# CrowPanel_ESP32_Display-7_0-inch-V3_0-20.net
KiCad netlist of a schematic drawn in EAGLE
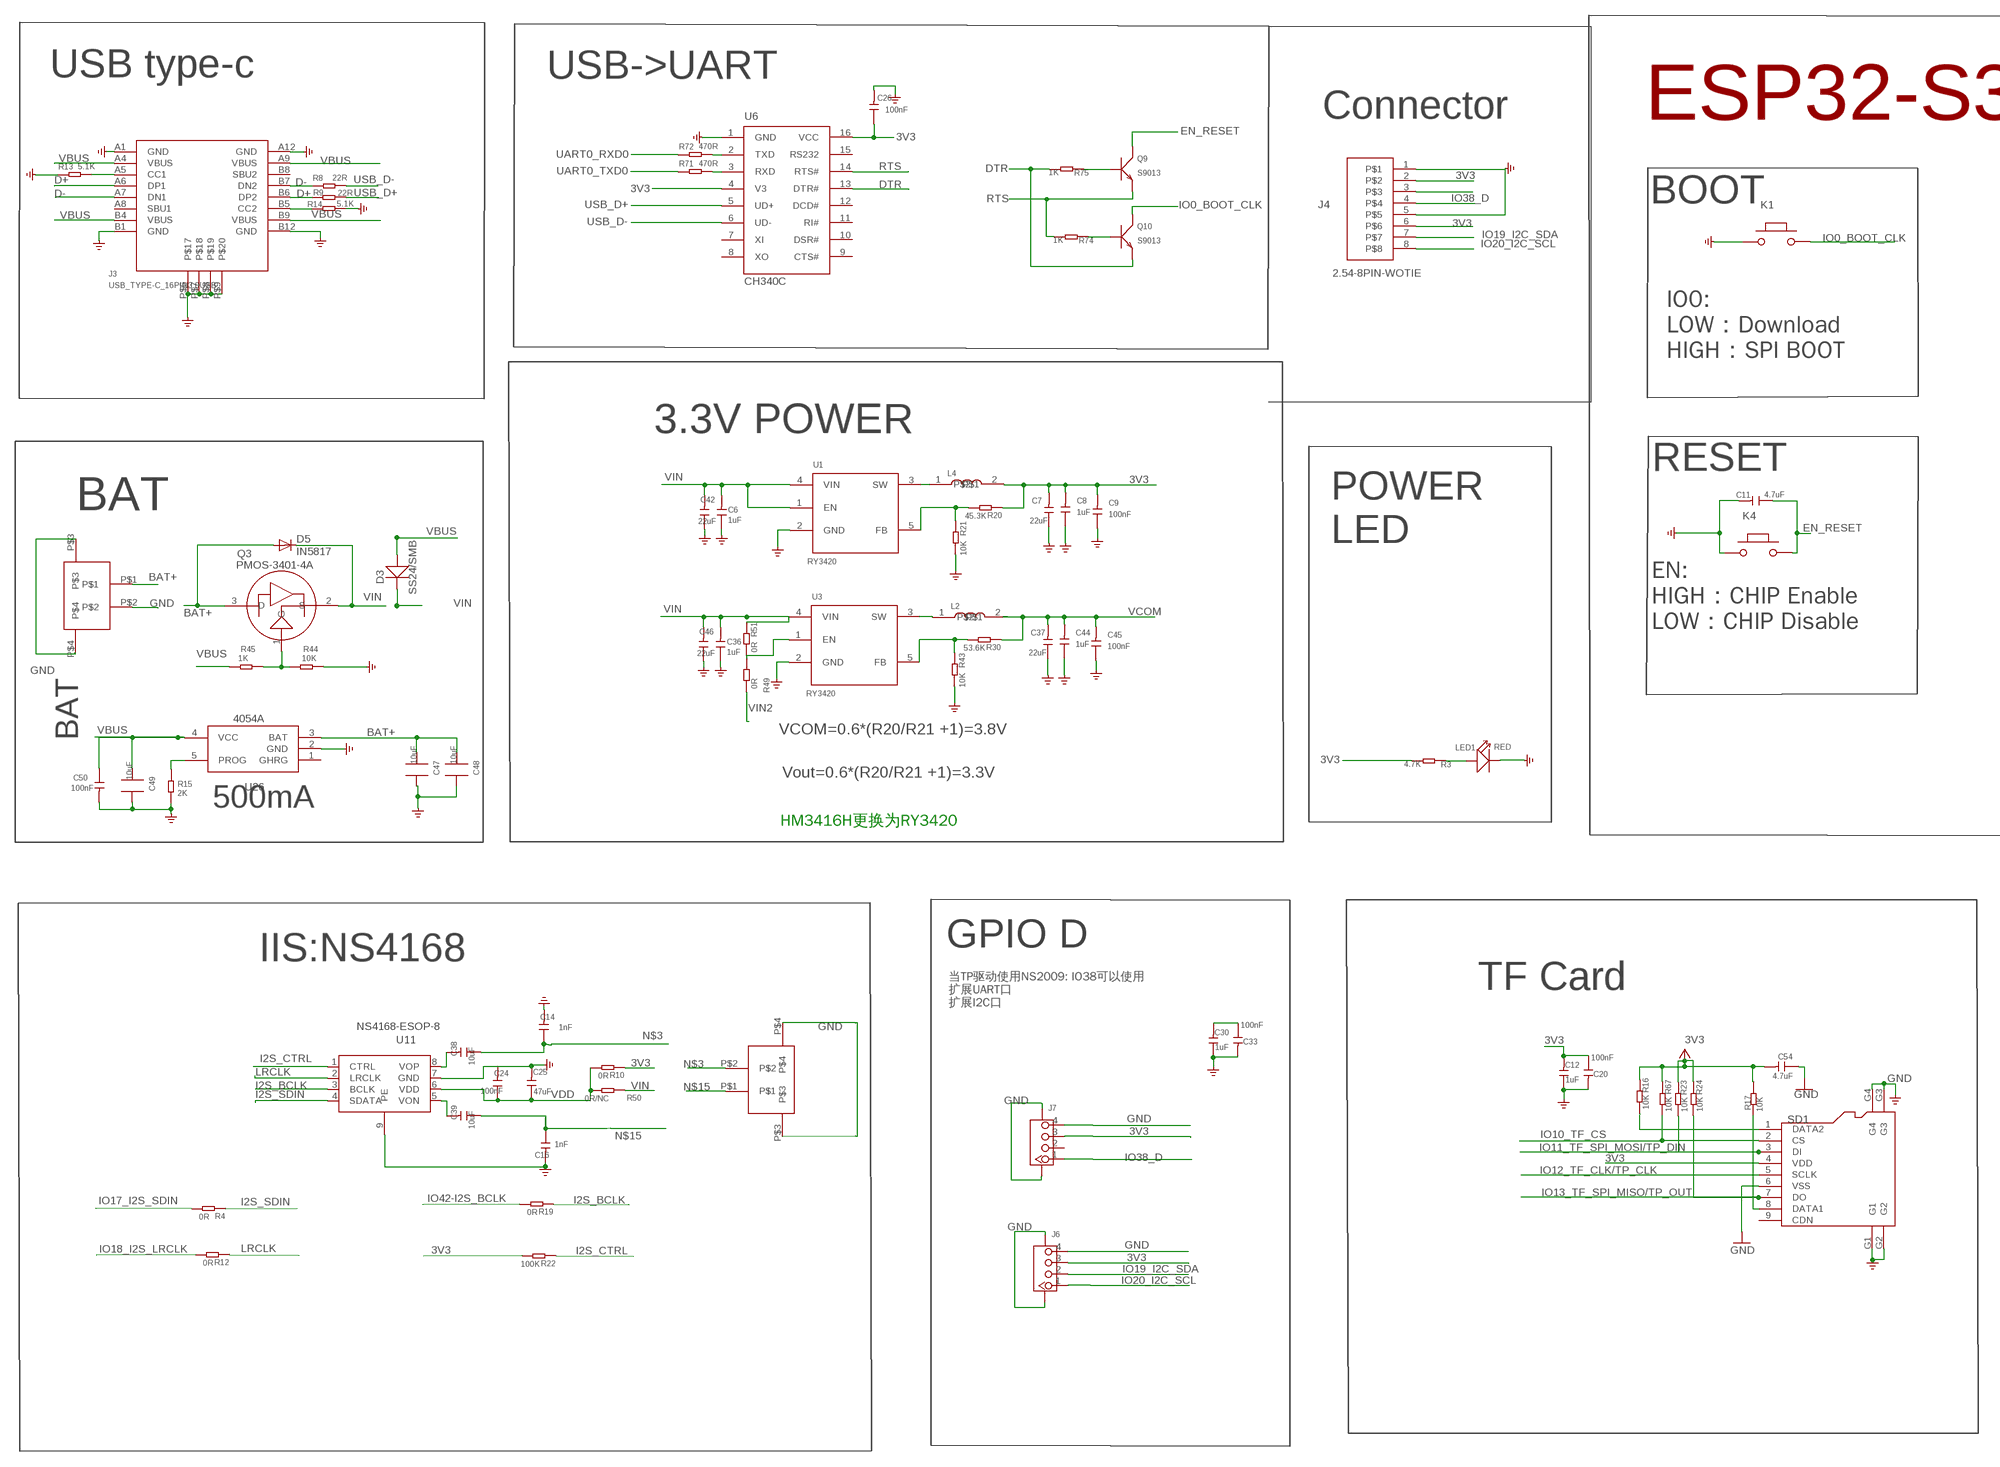
[diagram p0: schematic, sheet 1, part 1 of 2]
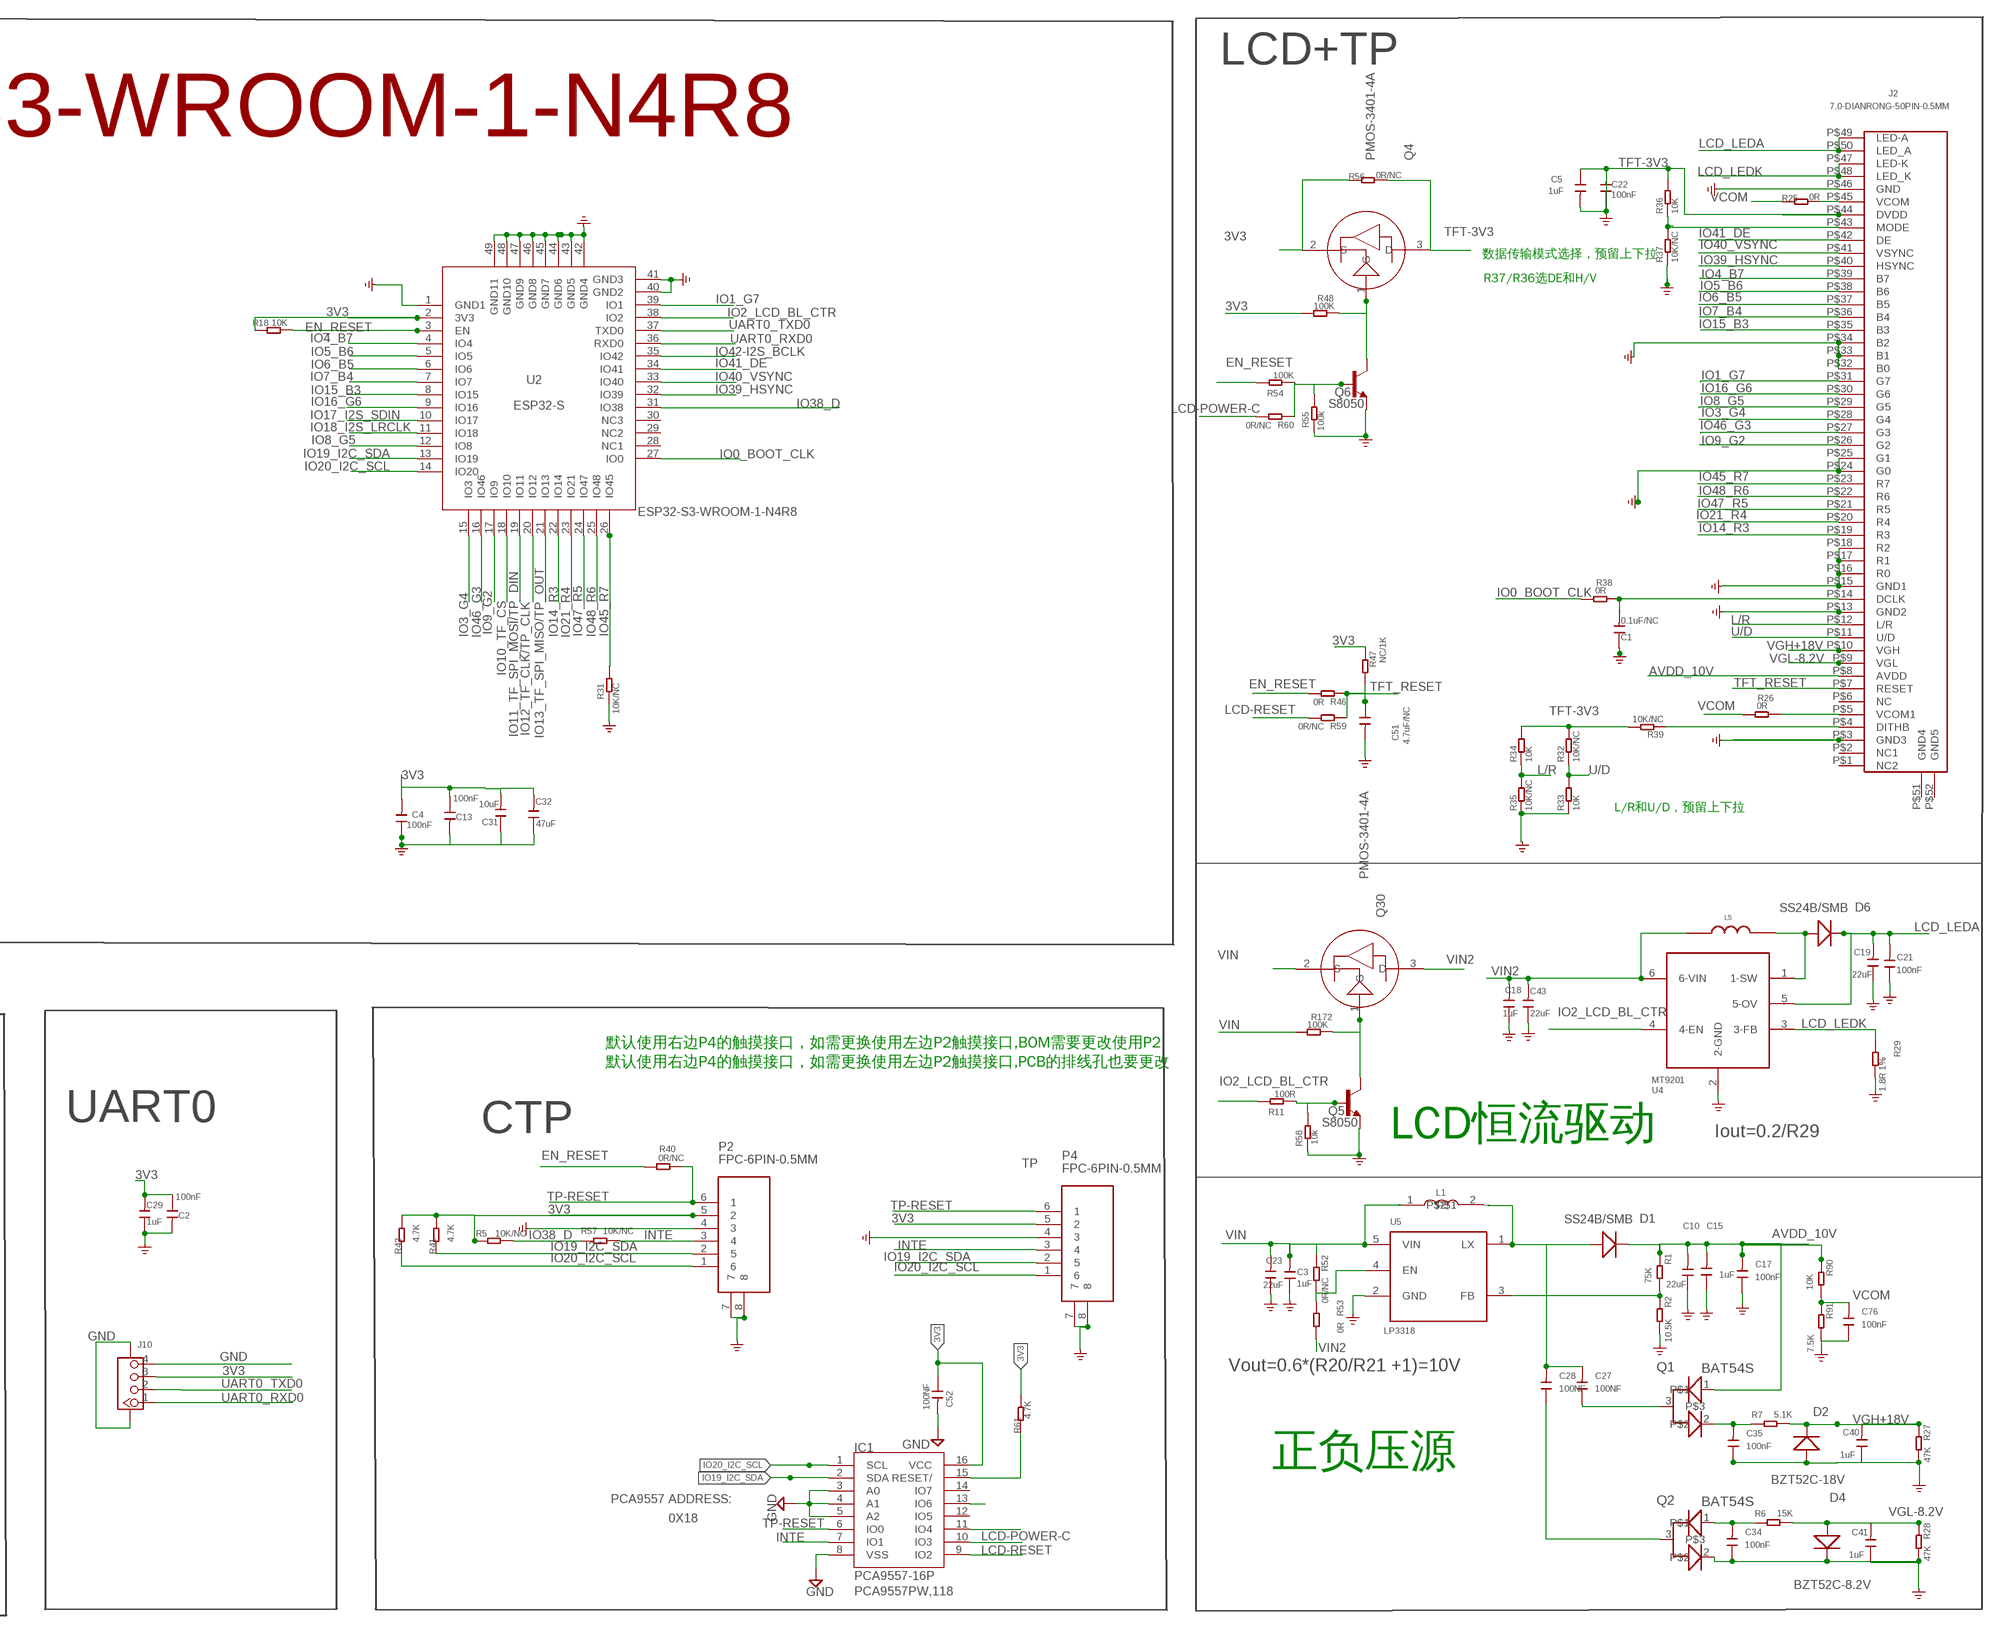
[diagram p1: schematic, sheet 1, part 2 of 2]

(export (version "E")
  (design (tool "Eeschema 10.0.6"))
  (components
    (comp (ref "C1")
      (value "0.1uF/NC")
      (footprint "eagle-import:DISCRETE_C0603")
      (libsource (lib "eagle-import") (part "DISCRETE_C-0603"))
    )
    (comp (ref "C2")
      (value "100nF")
      (footprint "eagle-import:C0603")
      (libsource (lib "eagle-import") (part "C-0603"))
    )
    (comp (ref "C3")
      (value "1uF")
      (footprint "eagle-import:0603")
      (libsource (lib "eagle-import") (part "C0603"))
    )
    (comp (ref "C4")
      (value "100nF")
      (footprint "eagle-import:C0603")
      (libsource (lib "eagle-import") (part "C-0603"))
    )
    (comp (ref "C5")
      (value "1uF")
      (footprint "eagle-import:C0603")
      (libsource (lib "eagle-import") (part "C-0603"))
    )
    (comp (ref "C6")
      (value "1uF")
      (footprint "eagle-import:0603")
      (libsource (lib "eagle-import") (part "C0603"))
    )
    (comp (ref "C7")
      (value "22uF")
      (footprint "eagle-import:0805")
      (libsource (lib "eagle-import") (part "C0805"))
    )
    (comp (ref "C8")
      (value "1uF")
      (footprint "eagle-import:0603")
      (libsource (lib "eagle-import") (part "C0603"))
    )
    (comp (ref "C9")
      (value "100nF")
      (footprint "eagle-import:0603")
      (libsource (lib "eagle-import") (part "C0603"))
    )
    (comp (ref "C10")
      (value "22uF")
      (footprint "eagle-import:0805")
      (libsource (lib "eagle-import") (part "C0805"))
    )
    (comp (ref "C11")
      (value "4.7uF")
      (footprint "eagle-import:0603")
      (libsource (lib "eagle-import") (part "C0603"))
    )
    (comp (ref "C12")
      (value "1uF")
      (footprint "eagle-import:DISCRETE_C0603")
      (libsource (lib "eagle-import") (part "A_xbj_DISCRETE_C-0603"))
    )
    (comp (ref "C13")
      (value "100nF")
      (footprint "eagle-import:C0603")
      (libsource (lib "eagle-import") (part "C-0603"))
    )
    (comp (ref "C14")
      (value "1nF")
      (footprint "eagle-import:C0603")
      (libsource (lib "eagle-import") (part "C-0603"))
    )
    (comp (ref "C15")
      (value "1uF")
      (footprint "eagle-import:0603")
      (libsource (lib "eagle-import") (part "C0603"))
    )
    (comp (ref "C16")
      (value "1nF")
      (footprint "eagle-import:C0603")
      (libsource (lib "eagle-import") (part "C-0603"))
    )
    (comp (ref "C17")
      (value "100nF")
      (footprint "eagle-import:0603")
      (libsource (lib "eagle-import") (part "C0603"))
    )
    (comp (ref "C18")
      (value "1uF")
      (footprint "eagle-import:0603")
      (libsource (lib "eagle-import") (part "C0603"))
    )
    (comp (ref "C19")
      (value "22uF")
      (footprint "eagle-import:0805")
      (libsource (lib "eagle-import") (part "C0805"))
    )
    (comp (ref "C20")
      (value "100nF")
      (footprint "eagle-import:C0603")
      (libsource (lib "eagle-import") (part "C-0603"))
    )
    (comp (ref "C21")
      (value "100nF")
      (footprint "eagle-import:0603")
      (libsource (lib "eagle-import") (part "C0603"))
    )
    (comp (ref "C22")
      (value "100nF")
      (footprint "eagle-import:C0603")
      (libsource (lib "eagle-import") (part "C-0603"))
    )
    (comp (ref "C23")
      (value "22uF")
      (footprint "eagle-import:0805")
      (libsource (lib "eagle-import") (part "C0805"))
    )
    (comp (ref "C24")
      (value "100nF")
      (footprint "eagle-import:C0603")
      (libsource (lib "eagle-import") (part "C-0603"))
    )
    (comp (ref "C25")
      (value "47uF")
      (footprint "eagle-import:0805")
      (libsource (lib "eagle-import") (part "C0805"))
    )
    (comp (ref "C26")
      (value "100nF")
      (footprint "eagle-import:0603")
      (libsource (lib "eagle-import") (part "C0603"))
    )
    (comp (ref "C27")
      (value "100NF")
      (footprint "eagle-import:0603")
      (libsource (lib "eagle-import") (part "C0603"))
    )
    (comp (ref "C28")
      (value "100NF")
      (footprint "eagle-import:0603")
      (libsource (lib "eagle-import") (part "C0603"))
    )
    (comp (ref "C29")
      (value "1uF")
      (footprint "eagle-import:DISCRETE_C0603")
      (libsource (lib "eagle-import") (part "A_xbj_DISCRETE_C-0603"))
    )
    (comp (ref "C30")
      (value "1uF")
      (footprint "eagle-import:DISCRETE_C0603")
      (libsource (lib "eagle-import") (part "A_xbj_DISCRETE_C-0603"))
    )
    (comp (ref "C31")
      (value "10uF")
      (footprint "eagle-import:DISCRETE_C0603")
      (libsource (lib "eagle-import") (part "DISCRETE_C-0603"))
    )
    (comp (ref "C32")
      (value "47uF")
      (footprint "eagle-import:0805")
      (libsource (lib "eagle-import") (part "C0805"))
    )
    (comp (ref "C33")
      (value "100nF")
      (footprint "eagle-import:C0603")
      (libsource (lib "eagle-import") (part "C-0603"))
    )
    (comp (ref "C34")
      (value "100nF")
      (footprint "eagle-import:0603")
      (libsource (lib "eagle-import") (part "C0603"))
    )
    (comp (ref "C35")
      (value "100nF")
      (footprint "eagle-import:0603")
      (libsource (lib "eagle-import") (part "C0603"))
    )
    (comp (ref "C36")
      (value "1uF")
      (footprint "eagle-import:0603")
      (libsource (lib "eagle-import") (part "C0603"))
    )
    (comp (ref "C37")
      (value "22uF")
      (footprint "eagle-import:0805")
      (libsource (lib "eagle-import") (part "C0805"))
    )
    (comp (ref "C38")
      (value "10uF")
      (footprint "eagle-import:C0603")
      (libsource (lib "eagle-import") (part "C-0603"))
    )
    (comp (ref "C39")
      (value "10uF")
      (footprint "eagle-import:C0603")
      (libsource (lib "eagle-import") (part "C-0603"))
    )
    (comp (ref "C40")
      (value "1uF")
      (footprint "eagle-import:0805")
      (libsource (lib "eagle-import") (part "C0805"))
    )
    (comp (ref "C41")
      (value "1uF")
      (footprint "eagle-import:0805")
      (libsource (lib "eagle-import") (part "C0805"))
    )
    (comp (ref "C42")
      (value "22uF")
      (footprint "eagle-import:0805")
      (libsource (lib "eagle-import") (part "C0805"))
    )
    (comp (ref "C43")
      (value "22uF")
      (footprint "eagle-import:0805")
      (libsource (lib "eagle-import") (part "C0805"))
    )
    (comp (ref "C44")
      (value "1uF")
      (footprint "eagle-import:0603")
      (libsource (lib "eagle-import") (part "C0603"))
    )
    (comp (ref "C45")
      (value "100nF")
      (footprint "eagle-import:0603")
      (libsource (lib "eagle-import") (part "C0603"))
    )
    (comp (ref "C46")
      (value "22uF")
      (footprint "eagle-import:0805")
      (libsource (lib "eagle-import") (part "C0805"))
    )
    (comp (ref "C47")
      (value "10uF")
      (footprint "eagle-import:0805_S")
      (libsource (lib "eagle-import") (part "C0805_S"))
    )
    (comp (ref "C48")
      (value "10uF")
      (footprint "eagle-import:0805_S")
      (libsource (lib "eagle-import") (part "C0805_S"))
    )
    (comp (ref "C49")
      (value "10uF")
      (footprint "eagle-import:0805_S")
      (libsource (lib "eagle-import") (part "C0805_S"))
    )
    (comp (ref "C50")
      (value "100nF")
      (footprint "eagle-import:C0603")
      (libsource (lib "eagle-import") (part "C-0603"))
    )
    (comp (ref "C51")
      (value "4.7uF/NC")
      (footprint "eagle-import:0603")
      (libsource (lib "eagle-import") (part "C0603"))
    )
    (comp (ref "C52")
      (value "100NF")
      (footprint "eagle-import:A_XBJ_0603")
      (libsource (lib "eagle-import") (part "A_XBJ_C0603"))
    )
    (comp (ref "C54")
      (value "4.7uF")
      (footprint "eagle-import:DISCRETE_C0603")
      (libsource (lib "eagle-import") (part "DISCRETE_C-0603"))
    )
    (comp (ref "C76")
      (value "100nF")
      (footprint "eagle-import:0603")
      (libsource (lib "eagle-import") (part "C0603"))
    )
    (comp (ref "D1")
      (value "SS24B/SMB")
      (footprint "eagle-import:214AB")
      (libsource (lib "eagle-import") (part "214ABDO-214AB"))
    )
    (comp (ref "D2")
      (value "BZT52C-18V")
      (footprint "eagle-import:DISCRETE_SOD123")
      (libsource (lib "eagle-import") (part "DISCRETE_D1206"))
    )
    (comp (ref "D3")
      (value "SS24/SMB")
      (footprint "eagle-import:214AB")
      (libsource (lib "eagle-import") (part "214ABDO-214AB"))
    )
    (comp (ref "D4")
      (value "BZT52C-8.2V")
      (footprint "eagle-import:DISCRETE_SOD123")
      (libsource (lib "eagle-import") (part "DISCRETE_D1206"))
    )
    (comp (ref "D5")
      (value "IN5817")
      (footprint "eagle-import:DO-214AC")
      (libsource (lib "eagle-import") (part "DIODE-DO-214AC"))
    )
    (comp (ref "D6")
      (value "SS24B/SMB")
      (footprint "eagle-import:214AB")
      (libsource (lib "eagle-import") (part "214ABDO-214AB"))
    )
    (comp (ref "IC1")
      (value "PCA9557-16P")
      (footprint "eagle-import:TSSOP16")
      (libsource (lib "eagle-import") (part "PCA9557-16P"))
    )
    (comp (ref "J1")
      (value "PH2.0WT-2PIN")
      (footprint "eagle-import:PH2.0WT-2PIN")
      (libsource (lib "eagle-import") (part "PH2.0WT-2PIN"))
    )
    (comp (ref "J2")
      (value "7.0-DIANRONG-50PIN-0.5MM")
      (footprint "eagle-import:7.0-DAINRONG-50PIN-0.5MM")
      (libsource (lib "eagle-import") (part "7.0-DIANRONG-50PIN-0.5MM"))
    )
    (comp (ref "J3")
      (value "USB_TYPE-C_16PIN3.0USB")
      (footprint "eagle-import:KEVIN_3.0TYPEC-SMD")
      (libsource (lib "eagle-import") (part "USB_TYPE-C_16PIN3.0USB"))
    )
    (comp (ref "J4")
      (value "2.54-8PIN-WOTIE")
      (footprint "eagle-import:2.54-8P-WOTIE")
      (libsource (lib "eagle-import") (part "2.54-8PIN-WOTIE"))
    )
    (comp (ref "J5")
      (value "PH2.0WT-2PIN")
      (footprint "eagle-import:PH2.0WT-2PIN")
      (libsource (lib "eagle-import") (part "PH2.0WT-2PIN"))
    )
    (comp (ref "J6")
      (value "CONNECTOR_TWIG-4P-2.0-SMD-FEMALE-REINFORCE90D")
      (footprint "eagle-import:CONNECTOR_4P-SMD-2.0-90D")
      (libsource (lib "eagle-import") (part "CONNECTOR_TWIG-4P-2.0-SMD-FEMALE-REINFORCE90D"))
    )
    (comp (ref "J7")
      (value "CONNECTOR_TWIG-4P-2.0-SMD-FEMALE-REINFORCE90D")
      (footprint "eagle-import:CONNECTOR_4P-SMD-2.0-90D")
      (libsource (lib "eagle-import") (part "CONNECTOR_TWIG-4P-2.0-SMD-FEMALE-REINFORCE90D"))
    )
    (comp (ref "J10")
      (value "CONNECTOR_TWIG-4P-2.0-SMD-FEMALE-REINFORCE90D")
      (footprint "eagle-import:CONNECTOR_4P-SMD-2.0-90D")
      (libsource (lib "eagle-import") (part "CONNECTOR_TWIG-4P-2.0-SMD-FEMALE-REINFORCE90D"))
    )
    (comp (ref "K1")
      (value "BUTTON")
      (footprint "eagle-import:157SW")
      (libsource (lib "eagle-import") (part "PB157"))
    )
    (comp (ref "K4")
      (value "BUTTON")
      (footprint "eagle-import:157SW")
      (libsource (lib "eagle-import") (part "PB157"))
    )
    (comp (ref "L1")
      (value "L-0530")
      (footprint "eagle-import:CD54_CD54")
      (libsource (lib "eagle-import") (part "L-0530"))
    )
    (comp (ref "L2")
      (value "L-0530")
      (footprint "eagle-import:CD54_CD54")
      (libsource (lib "eagle-import") (part "L-0530"))
    )
    (comp (ref "L4")
      (value "L-0530")
      (footprint "eagle-import:CD54_CD54")
      (libsource (lib "eagle-import") (part "L-0530"))
    )
    (comp (ref "L5")
      (value "CD32_6.8uH")
      (footprint "eagle-import:CD32")
      (libsource (lib "eagle-import") (part "CD32_950MA"))
    )
    (comp (ref "LED1")
      (value "RED")
      (footprint "eagle-import:DISCRETE_LED-0603")
      (libsource (lib "eagle-import") (part "DISCRETE_LED0603"))
    )
    (comp (ref "P2")
      (value "FPC-6PIN-0.5MM")
      (footprint "eagle-import:FPC-6PIN-0.5MM")
      (libsource (lib "eagle-import") (part "FPC-6PIN-0.5MM"))
    )
    (comp (ref "P4")
      (value "FPC-6PIN-0.5MM")
      (footprint "eagle-import:FPC-6PIN-0.5MM")
      (libsource (lib "eagle-import") (part "FPC-6PIN-0.5MM"))
    )
    (comp (ref "Q1")
      (value "BAT54S")
      (footprint "eagle-import:SOT23-3")
      (libsource (lib "eagle-import") (part "BAT54S"))
    )
    (comp (ref "Q2")
      (value "BAT54S")
      (footprint "eagle-import:SOT23-3")
      (libsource (lib "eagle-import") (part "BAT54S"))
    )
    (comp (ref "Q3")
      (value "PMOS-3401-4A")
      (footprint "eagle-import:SOT-23")
      (libsource (lib "eagle-import") (part "P-MOS-SOT23"))
    )
    (comp (ref "Q4")
      (value "PMOS-3401-4A")
      (footprint "eagle-import:SOT-23")
      (libsource (lib "eagle-import") (part "P-MOS-SOT23"))
    )
    (comp (ref "Q5")
      (value "S8050")
      (footprint "eagle-import:SPARKFUN_SOT23")
      (libsource (lib "eagle-import") (part "SPARKFUN_TRANSISTOR_NPNSOT23"))
    )
    (comp (ref "Q6")
      (value "S8050")
      (footprint "eagle-import:SPARKFUN_SOT23")
      (libsource (lib "eagle-import") (part "SPARKFUN_TRANSISTOR_NPNSOT23"))
    )
    (comp (ref "Q9")
      (value "S9013")
      (footprint "eagle-import:SOT23@1")
      (libsource (lib "eagle-import") (part "TRANSISTOR-NPN-SOT23"))
    )
    (comp (ref "Q10")
      (value "S9013")
      (footprint "eagle-import:SOT23@1")
      (libsource (lib "eagle-import") (part "TRANSISTOR-NPN-SOT23"))
    )
    (comp (ref "Q30")
      (value "PMOS-3401-4A")
      (footprint "eagle-import:SOT-23")
      (libsource (lib "eagle-import") (part "P-MOS-SOT23"))
    )
    (comp (ref "R1")
      (value "75K")
      (footprint "eagle-import:DISCRETE_R0603")
      (libsource (lib "eagle-import") (part "Crowtail-_LED-V2.0-20190615-01_DISCRETE_R-0603"))
    )
    (comp (ref "R2")
      (value "10.5K")
      (footprint "eagle-import:DISCRETE_R0603")
      (libsource (lib "eagle-import") (part "Crowtail-_LED-V2.0-20190615-01_DISCRETE_R-0603"))
    )
    (comp (ref "R3")
      (value "4.7K")
      (footprint "eagle-import:DISCRETE_R0603")
      (libsource (lib "eagle-import") (part "Crowtail-_LED-V2.0-20190615-01_DISCRETE_R-0603"))
    )
    (comp (ref "R4")
      (value "0R")
      (footprint "eagle-import:DISCRETE_R0603")
      (libsource (lib "eagle-import") (part "Crowtail-_LED-V2.0-20190615-01_DISCRETE_R-0603"))
    )
    (comp (ref "R5")
      (value "10K/NC")
      (footprint "eagle-import:DISCRETE_R0603")
      (libsource (lib "eagle-import") (part "Crowtail-_LED-V2.0-20190615-01_DISCRETE_R-0603"))
    )
    (comp (ref "R6")
      (value "15K")
      (footprint "eagle-import:DISCRETE_R0603")
      (libsource (lib "eagle-import") (part "Crowtail-_LED-V2.0-20190615-01_DISCRETE_R-0603"))
    )
    (comp (ref "R7")
      (value "5.1K")
      (footprint "eagle-import:DISCRETE_R0603")
      (libsource (lib "eagle-import") (part "Crowtail-_LED-V2.0-20190615-01_DISCRETE_R-0603"))
    )
    (comp (ref "R8")
      (value "22R")
      (footprint "eagle-import:DISCRETE_R0603")
      (libsource (lib "eagle-import") (part "Crowtail-_LED-V2.0-20190615-01_DISCRETE_R-0603"))
    )
    (comp (ref "R9")
      (value "22R")
      (footprint "eagle-import:DISCRETE_R0603")
      (libsource (lib "eagle-import") (part "Crowtail-_LED-V2.0-20190615-01_DISCRETE_R-0603"))
    )
    (comp (ref "R10")
      (value "0R")
      (footprint "eagle-import:DISCRETE_R0603")
      (libsource (lib "eagle-import") (part "Crowtail-_LED-V2.0-20190615-01_DISCRETE_R-0603"))
    )
    (comp (ref "R11")
      (value "100R")
      (footprint "eagle-import:R0603")
      (libsource (lib "eagle-import") (part "R0603"))
    )
    (comp (ref "R12")
      (value "0R")
      (footprint "eagle-import:DISCRETE_R0603")
      (libsource (lib "eagle-import") (part "Crowtail-_LED-V2.0-20190615-01_DISCRETE_R-0603"))
    )
    (comp (ref "R13")
      (value "5.1K")
      (footprint "eagle-import:DISCRETE_R0603")
      (libsource (lib "eagle-import") (part "Crowtail-_LED-V2.0-20190615-01_DISCRETE_R-0603"))
    )
    (comp (ref "R14")
      (value "5.1K")
      (footprint "eagle-import:DISCRETE_R0603")
      (libsource (lib "eagle-import") (part "Crowtail-_LED-V2.0-20190615-01_DISCRETE_R-0603"))
    )
    (comp (ref "R15")
      (value "2K")
      (footprint "eagle-import:DISCRETE_R0603")
      (libsource (lib "eagle-import") (part "DISCRETE_R-0603"))
    )
    (comp (ref "R16")
      (value "10K")
      (footprint "eagle-import:DISCRETE_R0603")
      (libsource (lib "eagle-import") (part "Crowtail-_LED-V2.0-20190615-01_DISCRETE_R-0603"))
    )
    (comp (ref "R17")
      (value "10K")
      (footprint "eagle-import:DISCRETE_R0603")
      (libsource (lib "eagle-import") (part "Crowtail-_LED-V2.0-20190615-01_DISCRETE_R-0603"))
    )
    (comp (ref "R18")
      (value "10K")
      (footprint "eagle-import:DISCRETE_R0603")
      (libsource (lib "eagle-import") (part "Crowtail-_LED-V2.0-20190615-01_DISCRETE_R-0603"))
    )
    (comp (ref "R19")
      (value "0R")
      (footprint "eagle-import:DISCRETE_R0603")
      (libsource (lib "eagle-import") (part "Crowtail-_LED-V2.0-20190615-01_DISCRETE_R-0603"))
    )
    (comp (ref "R20")
      (value "45.3K")
      (footprint "eagle-import:DISCRETE_R0603")
      (libsource (lib "eagle-import") (part "Crowtail-_LED-V2.0-20190615-01_DISCRETE_R-0603"))
    )
    (comp (ref "R21")
      (value "10K")
      (footprint "eagle-import:DISCRETE_R0603")
      (libsource (lib "eagle-import") (part "Crowtail-_LED-V2.0-20190615-01_DISCRETE_R-0603"))
    )
    (comp (ref "R22")
      (value "100K")
      (footprint "eagle-import:DISCRETE_R0603")
      (libsource (lib "eagle-import") (part "Crowtail-_LED-V2.0-20190615-01_DISCRETE_R-0603"))
    )
    (comp (ref "R23")
      (value "10K")
      (footprint "eagle-import:DISCRETE_R0603")
      (libsource (lib "eagle-import") (part "Crowtail-_LED-V2.0-20190615-01_DISCRETE_R-0603"))
    )
    (comp (ref "R24")
      (value "10K")
      (footprint "eagle-import:DISCRETE_R0603")
      (libsource (lib "eagle-import") (part "Crowtail-_LED-V2.0-20190615-01_DISCRETE_R-0603"))
    )
    (comp (ref "R25")
      (value "0R")
      (footprint "eagle-import:DISCRETE_R0603")
      (libsource (lib "eagle-import") (part "Crowtail-_LED-V2.0-20190615-01_DISCRETE_R-0603"))
    )
    (comp (ref "R26")
      (value "0R")
      (footprint "eagle-import:R0603")
      (libsource (lib "eagle-import") (part "R-0603"))
    )
    (comp (ref "R27")
      (value "47K")
      (footprint "eagle-import:DISCRETE_R0603")
      (libsource (lib "eagle-import") (part "Crowtail-_LED-V2.0-20190615-01_DISCRETE_R-0603"))
    )
    (comp (ref "R28")
      (value "47K")
      (footprint "eagle-import:DISCRETE_R0603")
      (libsource (lib "eagle-import") (part "Crowtail-_LED-V2.0-20190615-01_DISCRETE_R-0603"))
    )
    (comp (ref "R29")
      (value "1.8R 1%")
      (footprint "eagle-import:DISCRETE_R0603")
      (libsource (lib "eagle-import") (part "Crowtail-_LED-V2.0-20190615-01_DISCRETE_R-0603"))
    )
    (comp (ref "R30")
      (value "53.6K")
      (footprint "eagle-import:DISCRETE_R0603")
      (libsource (lib "eagle-import") (part "Crowtail-_LED-V2.0-20190615-01_DISCRETE_R-0603"))
    )
    (comp (ref "R31")
      (value "10K/NC")
      (footprint "eagle-import:R0603")
      (libsource (lib "eagle-import") (part "R0603"))
    )
    (comp (ref "R32")
      (value "10K/NC")
      (footprint "eagle-import:DISCRETE_R0603")
      (libsource (lib "eagle-import") (part "DISCRETE_R-0603"))
    )
    (comp (ref "R33")
      (value "10K")
      (footprint "eagle-import:DISCRETE_R0603")
      (libsource (lib "eagle-import") (part "DISCRETE_R-0603"))
    )
    (comp (ref "R34")
      (value "10K")
      (footprint "eagle-import:DISCRETE_R0603")
      (libsource (lib "eagle-import") (part "DISCRETE_R-0603"))
    )
    (comp (ref "R35")
      (value "10K/NC")
      (footprint "eagle-import:DISCRETE_R0603")
      (libsource (lib "eagle-import") (part "DISCRETE_R-0603"))
    )
    (comp (ref "R36")
      (value "10K")
      (footprint "eagle-import:DISCRETE_R0603")
      (libsource (lib "eagle-import") (part "DISCRETE_R-0603"))
    )
    (comp (ref "R37")
      (value "10K/NC")
      (footprint "eagle-import:DISCRETE_R0603")
      (libsource (lib "eagle-import") (part "DISCRETE_R-0603"))
    )
    (comp (ref "R38")
      (value "0R")
      (footprint "eagle-import:R0603")
      (libsource (lib "eagle-import") (part "R-0603"))
    )
    (comp (ref "R39")
      (value "10K/NC")
      (footprint "eagle-import:DISCRETE_R0603")
      (libsource (lib "eagle-import") (part "DISCRETE_R-0603"))
    )
    (comp (ref "R40")
      (value "0R/NC")
      (footprint "eagle-import:R0603")
      (libsource (lib "eagle-import") (part "R-0603"))
    )
    (comp (ref "R41")
      (value "4.7K")
      (footprint "eagle-import:DISCRETE_R0603")
      (libsource (lib "eagle-import") (part "Crowtail-_LED-V2.0-20190615-01_DISCRETE_R-0603"))
    )
    (comp (ref "R42")
      (value "4.7K")
      (footprint "eagle-import:DISCRETE_R0603")
      (libsource (lib "eagle-import") (part "Crowtail-_LED-V2.0-20190615-01_DISCRETE_R-0603"))
    )
    (comp (ref "R43")
      (value "10K")
      (footprint "eagle-import:DISCRETE_R0603")
      (libsource (lib "eagle-import") (part "Crowtail-_LED-V2.0-20190615-01_DISCRETE_R-0603"))
    )
    (comp (ref "R44")
      (value "10K")
      (footprint "eagle-import:DISCRETE_R0603")
      (libsource (lib "eagle-import") (part "DISCRETE_R-0603"))
    )
    (comp (ref "R45")
      (value "1K")
      (footprint "eagle-import:DISCRETE_R0603")
      (libsource (lib "eagle-import") (part "DISCRETE_R-0603"))
    )
    (comp (ref "R46")
      (value "0R")
      (footprint "eagle-import:DISCRETE_R0603")
      (libsource (lib "eagle-import") (part "Crowtail-_LED-V2.0-20190615-01_DISCRETE_R-0603"))
    )
    (comp (ref "R47")
      (value "NC/1K")
      (footprint "eagle-import:DISCRETE_R0603")
      (libsource (lib "eagle-import") (part "Crowtail-_LED-V2.0-20190615-01_DISCRETE_R-0603"))
    )
    (comp (ref "R48")
      (value "100K")
      (footprint "eagle-import:R0603")
      (libsource (lib "eagle-import") (part "R-0603"))
    )
    (comp (ref "R49")
      (value "0R")
      (footprint "eagle-import:DISCRETE_R0603")
      (libsource (lib "eagle-import") (part "Crowtail-_LED-V2.0-20190615-01_DISCRETE_R-0603"))
    )
    (comp (ref "R50")
      (value "0R/NC")
      (footprint "eagle-import:DISCRETE_R0603")
      (libsource (lib "eagle-import") (part "Crowtail-_LED-V2.0-20190615-01_DISCRETE_R-0603"))
    )
    (comp (ref "R51")
      (value "0R")
      (footprint "eagle-import:DISCRETE_R0603")
      (libsource (lib "eagle-import") (part "Crowtail-_LED-V2.0-20190615-01_DISCRETE_R-0603"))
    )
    (comp (ref "R52")
      (value "0R/NC")
      (footprint "eagle-import:DISCRETE_R0603")
      (libsource (lib "eagle-import") (part "Crowtail-_LED-V2.0-20190615-01_DISCRETE_R-0603"))
    )
    (comp (ref "R53")
      (value "0R")
      (footprint "eagle-import:DISCRETE_R0603")
      (libsource (lib "eagle-import") (part "Crowtail-_LED-V2.0-20190615-01_DISCRETE_R-0603"))
    )
    (comp (ref "R54")
      (value "100K")
      (footprint "eagle-import:R0603")
      (libsource (lib "eagle-import") (part "R0603"))
    )
    (comp (ref "R55")
      (value "100k")
      (footprint "eagle-import:R0603")
      (libsource (lib "eagle-import") (part "R0603"))
    )
    (comp (ref "R56")
      (value "0R/NC")
      (footprint "eagle-import:DISCRETE_R0603")
      (libsource (lib "eagle-import") (part "Crowtail-_LED-V2.0-20190615-01_DISCRETE_R-0603"))
    )
    (comp (ref "R57")
      (value "10K/NC")
      (footprint "eagle-import:DISCRETE_R0603")
      (libsource (lib "eagle-import") (part "Crowtail-_LED-V2.0-20190615-01_DISCRETE_R-0603"))
    )
    (comp (ref "R58")
      (value "10k")
      (footprint "eagle-import:R0603")
      (libsource (lib "eagle-import") (part "R0603"))
    )
    (comp (ref "R59")
      (value "0R/NC")
      (footprint "eagle-import:DISCRETE_R0603")
      (libsource (lib "eagle-import") (part "Crowtail-_LED-V2.0-20190615-01_DISCRETE_R-0603"))
    )
    (comp (ref "R60")
      (value "0R/NC")
      (footprint "eagle-import:DISCRETE_R0603")
      (libsource (lib "eagle-import") (part "Crowtail-_LED-V2.0-20190615-01_DISCRETE_R-0603"))
    )
    (comp (ref "R61")
      (value "4.7K")
      (footprint "eagle-import:DISCRETE_R0603")
      (libsource (lib "eagle-import") (part "Lora_RA-08H_Dev_DISCRETE_R-0603"))
    )
    (comp (ref "R67")
      (value "10K")
      (footprint "eagle-import:DISCRETE_R0603")
      (libsource (lib "eagle-import") (part "Crowtail-_LED-V2.0-20190615-01_DISCRETE_R-0603"))
    )
    (comp (ref "R71")
      (value "470R")
      (footprint "eagle-import:DISCRETE_R0603")
      (libsource (lib "eagle-import") (part "Crowtail-_LED-V2.0-20190615-01_DISCRETE_R-0603"))
    )
    (comp (ref "R72")
      (value "470R")
      (footprint "eagle-import:DISCRETE_R0603")
      (libsource (lib "eagle-import") (part "Crowtail-_LED-V2.0-20190615-01_DISCRETE_R-0603"))
    )
    (comp (ref "R74")
      (value "1K")
      (footprint "eagle-import:DISCRETE_R0603")
      (libsource (lib "eagle-import") (part "Crowtail-_LED-V2.0-20190615-01_DISCRETE_R-0603"))
    )
    (comp (ref "R75")
      (value "1K")
      (footprint "eagle-import:DISCRETE_R0603")
      (libsource (lib "eagle-import") (part "Crowtail-_LED-V2.0-20190615-01_DISCRETE_R-0603"))
    )
    (comp (ref "R90")
      (value "10K")
      (footprint "eagle-import:DISCRETE_R0603")
      (libsource (lib "eagle-import") (part "Crowtail-_LED-V2.0-20190615-01_DISCRETE_R-0603"))
    )
    (comp (ref "R91")
      (value "7.5K")
      (footprint "eagle-import:DISCRETE_R0603")
      (libsource (lib "eagle-import") (part "Crowtail-_LED-V2.0-20190615-01_DISCRETE_R-0603"))
    )
    (comp (ref "R172")
      (value "100K")
      (footprint "eagle-import:R0603")
      (libsource (lib "eagle-import") (part "R-0603"))
    )
    (comp (ref "SD1")
      (value "HOLDER-MICROSD-9P")
      (footprint "eagle-import:9P-SMD-W_-RING")
      (libsource (lib "eagle-import") (part "HOLDER-MICROSD-9P"))
    )
    (comp (ref "U1")
      (value "RY3420")
      (footprint "eagle-import:A_XBJ_SOT23-5")
      (libsource (lib "eagle-import") (part "A_XBJ_HM3420B"))
    )
    (comp (ref "U2")
      (value "ESP32-S")
      (footprint "eagle-import:ESP32-S3")
      (fields (field (name "U2") "ESP32-S3-WROOM-1-N4R8"))
      (libsource (lib "eagle-import") (part "ESP32-S"))
    )
    (comp (ref "U3")
      (value "RY3420")
      (footprint "eagle-import:A_XBJ_SOT23-5")
      (libsource (lib "eagle-import") (part "A_XBJ_HM3420B"))
    )
    (comp (ref "U4")
      (value "MT9201")
      (footprint "eagle-import:SOT23-6")
      (libsource (lib "eagle-import") (part "MT9201"))
    )
    (comp (ref "U5")
      (value "LP3318")
      (footprint "eagle-import:LP3318_SOT23-5")
      (libsource (lib "eagle-import") (part "LP3318"))
    )
    (comp (ref "U6")
      (value "CH340C")
      (footprint "eagle-import:SOP-16")
      (libsource (lib "eagle-import") (part "CH340G"))
    )
    (comp (ref "U11")
      (value "NS4168-ESOP-8")
      (footprint "eagle-import:NS4168-ESOP-8")
      (libsource (lib "eagle-import") (part "NS4168-ESOP-8"))
    )
    (comp (ref "U26")
      (value "4054A")
      (footprint "eagle-import:SOP23-5")
      (libsource (lib "eagle-import") (part "4054A"))
    )
  )
  (nets
    (net (code "1") (name "/AVDD_10V") (class "Default")
      (node (ref "C10") (pin "2") (pinfunction "2_2") (pintype "passive"))
      (node (ref "C15") (pin "2") (pinfunction "2_2") (pintype "passive"))
      (node (ref "C17") (pin "2") (pinfunction "2_2") (pintype "passive"))
      (node (ref "D1") (pin "2") (pinfunction "-_2") (pintype "passive"))
      (node (ref "J2") (pin "P$8") (pinfunction "AVDD_P$8") (pintype "bidirectional"))
      (node (ref "Q1") (pin "1") (pinfunction "P$1_1") (pintype "bidirectional"))
      (node (ref "R1") (pin "1") (pinfunction "1_1") (pintype "passive"))
      (node (ref "R90") (pin "1") (pinfunction "1_1") (pintype "passive"))
    )
    (net (code "2") (name "/BAT+") (class "Default")
      (node (ref "C47") (pin "2") (pinfunction "2_2") (pintype "bidirectional"))
      (node (ref "C48") (pin "2") (pinfunction "2_2") (pintype "bidirectional"))
      (node (ref "D5") (pin "A") (pinfunction "A_A") (pintype "passive"))
      (node (ref "J1") (pin "P$1") (pinfunction "P$1_P$1") (pintype "bidirectional"))
      (node (ref "Q3") (pin "3") (pinfunction "D_3") (pintype "bidirectional"))
      (node (ref "U26") (pin "3") (pinfunction "BAT_3") (pintype "bidirectional"))
    )
    (net (code "3") (name "/D+") (class "Default")
      (node (ref "J3") (pin "A6") (pinfunction "DP1_A6") (pintype "bidirectional"))
      (node (ref "J3") (pin "B6") (pinfunction "DP2_B6") (pintype "bidirectional"))
      (node (ref "R9") (pin "1") (pinfunction "1_1") (pintype "passive"))
    )
    (net (code "4") (name "/D-") (class "Default")
      (node (ref "J3") (pin "A7") (pinfunction "DN1_A7") (pintype "bidirectional"))
      (node (ref "J3") (pin "B7") (pinfunction "DN2_B7") (pintype "bidirectional"))
      (node (ref "R8") (pin "1") (pinfunction "1_1") (pintype "passive"))
    )
    (net (code "5") (name "/DTR") (class "Default")
      (node (ref "Q10") (pin "2") (pinfunction "E_2") (pintype "passive"))
      (node (ref "R75") (pin "2") (pinfunction "2_2") (pintype "passive"))
      (node (ref "U6") (pin "13") (pinfunction "DTR#_13") (pintype "bidirectional"))
    )
    (net (code "6") (name "/EN_RESET") (class "Default")
      (node (ref "C11") (pin "1") (pinfunction "1_1") (pintype "passive"))
      (node (ref "K4") (pin "2") (pinfunction "2_2") (pintype "passive"))
      (node (ref "Q9") (pin "3") (pinfunction "C_3") (pintype "passive"))
      (node (ref "R18") (pin "2") (pinfunction "2_2") (pintype "passive"))
      (node (ref "R40") (pin "1") (pinfunction "1_1") (pintype "passive"))
      (node (ref "R46") (pin "2") (pinfunction "2_2") (pintype "passive"))
      (node (ref "R54") (pin "2") (pinfunction "2_2") (pintype "passive"))
      (node (ref "U2") (pin "3") (pinfunction "EN_3") (pintype "bidirectional"))
    )
    (net (code "7") (name "/I2S_BCLK") (class "Default")
      (node (ref "R19") (pin "1") (pinfunction "1_1") (pintype "passive"))
      (node (ref "U11") (pin "3") (pinfunction "BCLK_3") (pintype "bidirectional"))
    )
    (net (code "8") (name "/I2S_CTRL") (class "Default")
      (node (ref "R22") (pin "1") (pinfunction "1_1") (pintype "passive"))
      (node (ref "U11") (pin "1") (pinfunction "CTRL_1") (pintype "bidirectional"))
    )
    (net (code "9") (name "/I2S_SDIN") (class "Default")
      (node (ref "R4") (pin "1") (pinfunction "1_1") (pintype "passive"))
      (node (ref "U11") (pin "4") (pinfunction "SDATA_4") (pintype "bidirectional"))
    )
    (net (code "10") (name "/INTE") (class "Default")
      (node (ref "IC1") (pin "7") (pinfunction "IO1_7") (pintype "bidirectional"))
      (node (ref "P2") (pin "3") (pinfunction "4_3") (pintype "bidirectional"))
      (node (ref "P4") (pin "3") (pinfunction "4_3") (pintype "bidirectional"))
      (node (ref "R57") (pin "2") (pinfunction "2_2") (pintype "passive"))
    )
    (net (code "11") (name "/IO0_BOOT_CLK") (class "Default")
      (node (ref "K1") (pin "2") (pinfunction "2_2") (pintype "passive"))
      (node (ref "Q10") (pin "3") (pinfunction "C_3") (pintype "passive"))
      (node (ref "R38") (pin "1") (pinfunction "1_1") (pintype "passive"))
      (node (ref "U2") (pin "27") (pinfunction "IO0_27") (pintype "bidirectional"))
    )
    (net (code "12") (name "/IO1_G7") (class "Default")
      (node (ref "J2") (pin "P$31") (pinfunction "G7_P$31") (pintype "bidirectional"))
      (node (ref "U2") (pin "39") (pinfunction "IO1_39") (pintype "bidirectional"))
    )
    (net (code "13") (name "/IO2_LCD_BL_CTR") (class "Default")
      (node (ref "R11") (pin "2") (pinfunction "2_2") (pintype "passive"))
      (node (ref "U2") (pin "38") (pinfunction "IO2_38") (pintype "bidirectional"))
      (node (ref "U4") (pin "4") (pinfunction "4-EN_4") (pintype "bidirectional"))
    )
    (net (code "14") (name "/IO3_G4") (class "Default")
      (node (ref "J2") (pin "P$28") (pinfunction "G4_P$28") (pintype "bidirectional"))
      (node (ref "U2") (pin "15") (pinfunction "IO3_15") (pintype "bidirectional"))
    )
    (net (code "15") (name "/IO4_B7") (class "Default")
      (node (ref "J2") (pin "P$39") (pinfunction "B7_P$39") (pintype "bidirectional"))
      (node (ref "U2") (pin "4") (pinfunction "IO4_4") (pintype "bidirectional"))
    )
    (net (code "16") (name "/IO5_B6") (class "Default")
      (node (ref "J2") (pin "P$38") (pinfunction "B6_P$38") (pintype "bidirectional"))
      (node (ref "U2") (pin "5") (pinfunction "IO5_5") (pintype "bidirectional"))
    )
    (net (code "17") (name "/IO6_B5") (class "Default")
      (node (ref "J2") (pin "P$37") (pinfunction "B5_P$37") (pintype "bidirectional"))
      (node (ref "U2") (pin "6") (pinfunction "IO6_6") (pintype "bidirectional"))
    )
    (net (code "18") (name "/IO7_B4") (class "Default")
      (node (ref "J2") (pin "P$36") (pinfunction "B4_P$36") (pintype "bidirectional"))
      (node (ref "U2") (pin "7") (pinfunction "IO7_7") (pintype "bidirectional"))
    )
    (net (code "19") (name "/IO8_G5") (class "Default")
      (node (ref "J2") (pin "P$29") (pinfunction "G5_P$29") (pintype "bidirectional"))
      (node (ref "U2") (pin "12") (pinfunction "IO8_12") (pintype "bidirectional"))
    )
    (net (code "20") (name "/IO9_G2") (class "Default")
      (node (ref "J2") (pin "P$26") (pinfunction "G2_P$26") (pintype "bidirectional"))
      (node (ref "U2") (pin "17") (pinfunction "IO9_17") (pintype "bidirectional"))
    )
    (net (code "21") (name "/IO10_TF_CS") (class "Default")
      (node (ref "R67") (pin "2") (pinfunction "2_2") (pintype "passive"))
      (node (ref "SD1") (pin "2") (pinfunction "CS_2") (pintype "bidirectional"))
      (node (ref "U2") (pin "18") (pinfunction "IO10_18") (pintype "bidirectional"))
    )
    (net (code "22") (name "/IO11_TF_SPI_MOSI{slash}TP_DIN") (class "Default")
      (node (ref "R23") (pin "2") (pinfunction "2_2") (pintype "passive"))
      (node (ref "SD1") (pin "3") (pinfunction "DI_3") (pintype "bidirectional"))
      (node (ref "U2") (pin "19") (pinfunction "IO11_19") (pintype "bidirectional"))
    )
    (net (code "23") (name "/IO12_TF_CLK{slash}TP_CLK") (class "Default")
      (node (ref "SD1") (pin "5") (pinfunction "SCLK_5") (pintype "bidirectional"))
      (node (ref "U2") (pin "20") (pinfunction "IO12_20") (pintype "bidirectional"))
    )
    (net (code "24") (name "/IO13_TF_SPI_MISO{slash}TP_OUT") (class "Default")
      (node (ref "R24") (pin "2") (pinfunction "2_2") (pintype "passive"))
      (node (ref "SD1") (pin "7") (pinfunction "DO_7") (pintype "bidirectional"))
      (node (ref "U2") (pin "21") (pinfunction "IO13_21") (pintype "bidirectional"))
    )
    (net (code "25") (name "/IO14_R3") (class "Default")
      (node (ref "J2") (pin "P$19") (pinfunction "R3_P$19") (pintype "bidirectional"))
      (node (ref "U2") (pin "22") (pinfunction "IO14_22") (pintype "bidirectional"))
    )
    (net (code "26") (name "/IO15_B3") (class "Default")
      (node (ref "J2") (pin "P$35") (pinfunction "B3_P$35") (pintype "bidirectional"))
      (node (ref "U2") (pin "8") (pinfunction "IO15_8") (pintype "bidirectional"))
    )
    (net (code "27") (name "/IO16_G6") (class "Default")
      (node (ref "J2") (pin "P$30") (pinfunction "G6_P$30") (pintype "bidirectional"))
      (node (ref "U2") (pin "9") (pinfunction "IO16_9") (pintype "bidirectional"))
    )
    (net (code "28") (name "/IO17_I2S_SDIN") (class "Default")
      (node (ref "R4") (pin "2") (pinfunction "2_2") (pintype "passive"))
      (node (ref "U2") (pin "10") (pinfunction "IO17_10") (pintype "bidirectional"))
    )
    (net (code "29") (name "/IO18_I2S_LRCLK") (class "Default")
      (node (ref "R12") (pin "2") (pinfunction "2_2") (pintype "passive"))
      (node (ref "U2") (pin "11") (pinfunction "IO18_11") (pintype "bidirectional"))
    )
    (net (code "30") (name "/IO21_R4") (class "Default")
      (node (ref "J2") (pin "P$20") (pinfunction "R4_P$20") (pintype "bidirectional"))
      (node (ref "U2") (pin "23") (pinfunction "IO21_23") (pintype "bidirectional"))
    )
    (net (code "31") (name "/IO38_D") (class "Default")
      (node (ref "J4") (pin "4") (pinfunction "P$4_4") (pintype "bidirectional"))
      (node (ref "J7") (pin "1") (pinfunction "1_1") (pintype "bidirectional"))
      (node (ref "R5") (pin "2") (pinfunction "2_2") (pintype "passive"))
      (node (ref "R57") (pin "1") (pinfunction "1_1") (pintype "passive"))
      (node (ref "U2") (pin "31") (pinfunction "IO38_31") (pintype "bidirectional"))
    )
    (net (code "32") (name "/IO39_HSYNC") (class "Default")
      (node (ref "J2") (pin "P$40") (pinfunction "HSYNC_P$40") (pintype "bidirectional"))
      (node (ref "U2") (pin "32") (pinfunction "IO39_32") (pintype "bidirectional"))
    )
    (net (code "33") (name "/IO40_VSYNC") (class "Default")
      (node (ref "J2") (pin "P$41") (pinfunction "VSYNC_P$41") (pintype "bidirectional"))
      (node (ref "U2") (pin "33") (pinfunction "IO40_33") (pintype "bidirectional"))
    )
    (net (code "34") (name "/IO41_DE") (class "Default")
      (node (ref "J2") (pin "P$42") (pinfunction "DE_P$42") (pintype "bidirectional"))
      (node (ref "U2") (pin "34") (pinfunction "IO41_34") (pintype "bidirectional"))
    )
    (net (code "35") (name "/IO42-I2S_BCLK") (class "Default")
      (node (ref "R19") (pin "2") (pinfunction "2_2") (pintype "passive"))
      (node (ref "U2") (pin "35") (pinfunction "IO42_35") (pintype "bidirectional"))
    )
    (net (code "36") (name "/IO45_R7") (class "Default")
      (node (ref "J2") (pin "P$23") (pinfunction "R7_P$23") (pintype "bidirectional"))
      (node (ref "R31") (pin "2") (pinfunction "2_2") (pintype "passive"))
      (node (ref "U2") (pin "26") (pinfunction "IO45_26") (pintype "bidirectional"))
    )
    (net (code "37") (name "/IO46_G3") (class "Default")
      (node (ref "J2") (pin "P$27") (pinfunction "G3_P$27") (pintype "bidirectional"))
      (node (ref "U2") (pin "16") (pinfunction "IO46_16") (pintype "bidirectional"))
    )
    (net (code "38") (name "/IO47_R5") (class "Default")
      (node (ref "J2") (pin "P$21") (pinfunction "R5_P$21") (pintype "bidirectional"))
      (node (ref "U2") (pin "24") (pinfunction "IO47_24") (pintype "bidirectional"))
    )
    (net (code "39") (name "/IO48_R6") (class "Default")
      (node (ref "J2") (pin "P$22") (pinfunction "R6_P$22") (pintype "bidirectional"))
      (node (ref "U2") (pin "25") (pinfunction "IO48_25") (pintype "bidirectional"))
    )
    (net (code "40") (name "/LCD-POWER-C") (class "Default")
      (node (ref "IC1") (pin "10") (pinfunction "IO3_10") (pintype "bidirectional"))
      (node (ref "R60") (pin "2") (pinfunction "2_2") (pintype "passive"))
    )
    (net (code "41") (name "/LCD-RESET") (class "Default")
      (node (ref "IC1") (pin "9") (pinfunction "IO2_9") (pintype "bidirectional"))
      (node (ref "R59") (pin "2") (pinfunction "2_2") (pintype "passive"))
    )
    (net (code "42") (name "/LCD_LEDA") (class "Default")
      (node (ref "C19") (pin "2") (pinfunction "2_2") (pintype "passive"))
      (node (ref "C21") (pin "2") (pinfunction "2_2") (pintype "passive"))
      (node (ref "D6") (pin "2") (pinfunction "-_2") (pintype "passive"))
      (node (ref "J2") (pin "P$49") (pinfunction "LED-A_P$49") (pintype "bidirectional"))
      (node (ref "J2") (pin "P$50") (pinfunction "LED_A_P$50") (pintype "bidirectional"))
      (node (ref "U4") (pin "5") (pinfunction "5-OV_5") (pintype "bidirectional"))
    )
    (net (code "43") (name "/LCD_LEDK") (class "Default")
      (node (ref "J2") (pin "P$47") (pinfunction "LED-K_P$47") (pintype "bidirectional"))
      (node (ref "J2") (pin "P$48") (pinfunction "LED_K_P$48") (pintype "bidirectional"))
      (node (ref "R29") (pin "1") (pinfunction "1_1") (pintype "passive"))
      (node (ref "U4") (pin "3") (pinfunction "3-FB_3") (pintype "bidirectional"))
    )
    (net (code "44") (name "/LRCLK") (class "Default")
      (node (ref "R12") (pin "1") (pinfunction "1_1") (pintype "passive"))
      (node (ref "U11") (pin "2") (pinfunction "LRCLK_2") (pintype "bidirectional"))
    )
    (net (code "45") (name "/L{slash}R") (class "Default")
      (node (ref "J2") (pin "P$12") (pinfunction "L/R_P$12") (pintype "bidirectional"))
      (node (ref "R34") (pin "1") (pinfunction "1_1") (pintype "passive"))
      (node (ref "R35") (pin "2") (pinfunction "2_2") (pintype "passive"))
    )
    (net (code "46") (name "/N$3") (class "Default")
      (node (ref "C14") (pin "1") (pinfunction "1_1") (pintype "passive"))
      (node (ref "C38") (pin "1") (pinfunction "1_1") (pintype "passive"))
      (node (ref "J5") (pin "P$2") (pinfunction "P$2_P$2") (pintype "bidirectional"))
    )
    (net (code "47") (name "/N$15") (class "Default")
      (node (ref "C16") (pin "1") (pinfunction "1_1") (pintype "passive"))
      (node (ref "C39") (pin "1") (pinfunction "1_1") (pintype "passive"))
      (node (ref "J5") (pin "P$1") (pinfunction "P$1_P$1") (pintype "bidirectional"))
    )
    (net (code "48") (name "/RTS") (class "Default")
      (node (ref "Q9") (pin "2") (pinfunction "E_2") (pintype "passive"))
      (node (ref "R74") (pin "2") (pinfunction "2_2") (pintype "passive"))
      (node (ref "U6") (pin "14") (pinfunction "RTS#_14") (pintype "bidirectional"))
    )
    (net (code "49") (name "/TFT-3V3") (class "Default")
      (node (ref "C22") (pin "2") (pinfunction "2_2") (pintype "passive"))
      (node (ref "C5") (pin "1") (pinfunction "1_1") (pintype "passive"))
      (node (ref "J2") (pin "P$44") (pinfunction "DVDD_P$44") (pintype "bidirectional"))
      (node (ref "Q4") (pin "3") (pinfunction "D_3") (pintype "bidirectional"))
      (node (ref "R32") (pin "2") (pinfunction "2_2") (pintype "passive"))
      (node (ref "R34") (pin "2") (pinfunction "2_2") (pintype "passive"))
      (node (ref "R36") (pin "2") (pinfunction "2_2") (pintype "passive"))
      (node (ref "R39") (pin "2") (pinfunction "2_2") (pintype "passive"))
      (node (ref "R56") (pin "2") (pinfunction "2_2") (pintype "passive"))
    )
    (net (code "50") (name "/TFT_RESET") (class "Default")
      (node (ref "C51") (pin "1") (pinfunction "1_1") (pintype "passive"))
      (node (ref "J2") (pin "P$7") (pinfunction "RESET_P$7") (pintype "bidirectional"))
      (node (ref "R46") (pin "1") (pinfunction "1_1") (pintype "passive"))
      (node (ref "R47") (pin "1") (pinfunction "1_1") (pintype "passive"))
      (node (ref "R59") (pin "1") (pinfunction "1_1") (pintype "passive"))
    )
    (net (code "51") (name "/TP-RESET") (class "Default")
      (node (ref "IC1") (pin "6") (pinfunction "IO0_6") (pintype "bidirectional"))
      (node (ref "P2") (pin "6") (pinfunction "1_6") (pintype "bidirectional"))
      (node (ref "P4") (pin "6") (pinfunction "1_6") (pintype "bidirectional"))
      (node (ref "R40") (pin "2") (pinfunction "2_2") (pintype "passive"))
    )
    (net (code "52") (name "/UART0_RXD0") (class "Default")
      (node (ref "J10") (pin "1") (pinfunction "1_1") (pintype "bidirectional"))
      (node (ref "R72") (pin "1") (pinfunction "1_1") (pintype "passive"))
      (node (ref "U2") (pin "36") (pinfunction "RXD0_36") (pintype "bidirectional"))
    )
    (net (code "53") (name "/UART0_TXD0") (class "Default")
      (node (ref "J10") (pin "2") (pinfunction "2_2") (pintype "bidirectional"))
      (node (ref "R71") (pin "1") (pinfunction "1_1") (pintype "passive"))
      (node (ref "U2") (pin "37") (pinfunction "TXD0_37") (pintype "bidirectional"))
    )
    (net (code "54") (name "/USB_D+") (class "Default")
      (node (ref "R9") (pin "2") (pinfunction "2_2") (pintype "passive"))
      (node (ref "U6") (pin "5") (pinfunction "UD+_5") (pintype "bidirectional"))
    )
    (net (code "55") (name "/USB_D-") (class "Default")
      (node (ref "R8") (pin "2") (pinfunction "2_2") (pintype "passive"))
      (node (ref "U6") (pin "6") (pinfunction "UD-_6") (pintype "bidirectional"))
    )
    (net (code "56") (name "/U{slash}D") (class "Default")
      (node (ref "J2") (pin "P$11") (pinfunction "U/D_P$11") (pintype "bidirectional"))
      (node (ref "R32") (pin "1") (pinfunction "1_1") (pintype "passive"))
      (node (ref "R33") (pin "2") (pinfunction "2_2") (pintype "passive"))
    )
    (net (code "57") (name "/VBUS") (class "Default")
      (node (ref "C49") (pin "2") (pinfunction "2_2") (pintype "bidirectional"))
      (node (ref "C50") (pin "1") (pinfunction "1_1") (pintype "passive"))
      (node (ref "D3") (pin "1") (pinfunction "+_1") (pintype "passive"))
      (node (ref "J3") (pin "A4") (pinfunction "VBUS_A4") (pintype "bidirectional"))
      (node (ref "J3") (pin "A9") (pinfunction "VBUS_A9") (pintype "bidirectional"))
      (node (ref "J3") (pin "B4") (pinfunction "VBUS_B4") (pintype "bidirectional"))
      (node (ref "J3") (pin "B9") (pinfunction "VBUS_B9") (pintype "bidirectional"))
      (node (ref "R45") (pin "2") (pinfunction "2_2") (pintype "passive"))
      (node (ref "U26") (pin "4") (pinfunction "VCC_4") (pintype "bidirectional"))
    )
    (net (code "58") (name "/VCOM") (class "Default")
      (node (ref "C37") (pin "2") (pinfunction "2_2") (pintype "passive"))
      (node (ref "C44") (pin "2") (pinfunction "2_2") (pintype "passive"))
      (node (ref "C45") (pin "2") (pinfunction "2_2") (pintype "passive"))
      (node (ref "C76") (pin "2") (pinfunction "2_2") (pintype "passive"))
      (node (ref "L2") (pin "2") (pinfunction "P$2_2") (pintype "bidirectional"))
      (node (ref "R25") (pin "1") (pinfunction "1_1") (pintype "passive"))
      (node (ref "R26") (pin "1") (pinfunction "1_1") (pintype "passive"))
      (node (ref "R30") (pin "1") (pinfunction "1_1") (pintype "passive"))
      (node (ref "R90") (pin "2") (pinfunction "2_2") (pintype "passive"))
      (node (ref "R91") (pin "1") (pinfunction "1_1") (pintype "passive"))
    )
    (net (code "59") (name "/VDD") (class "Default")
      (node (ref "C24") (pin "1") (pinfunction "1_1") (pintype "passive"))
      (node (ref "C25") (pin "1") (pinfunction "1_1") (pintype "passive"))
      (node (ref "R10") (pin "2") (pinfunction "2_2") (pintype "passive"))
      (node (ref "R50") (pin "2") (pinfunction "2_2") (pintype "passive"))
      (node (ref "U11") (pin "6") (pinfunction "VDD_6") (pintype "bidirectional"))
    )
    (net (code "60") (name "/VGH+18V") (class "Default")
      (node (ref "C40") (pin "2") (pinfunction "2_2") (pintype "passive"))
      (node (ref "D2") (pin "-") (pinfunction "-_-") (pintype "passive"))
      (node (ref "J2") (pin "P$10") (pinfunction "VGH_P$10") (pintype "bidirectional"))
      (node (ref "R27") (pin "1") (pinfunction "1_1") (pintype "passive"))
      (node (ref "R7") (pin "2") (pinfunction "2_2") (pintype "passive"))
    )
    (net (code "61") (name "/VGL-8.2V") (class "Default")
      (node (ref "C41") (pin "2") (pinfunction "2_2") (pintype "passive"))
      (node (ref "D4") (pin "+") (pinfunction "+_+") (pintype "passive"))
      (node (ref "J2") (pin "P$9") (pinfunction "VGL_P$9") (pintype "bidirectional"))
      (node (ref "R28") (pin "1") (pinfunction "1_1") (pintype "passive"))
      (node (ref "R6") (pin "2") (pinfunction "2_2") (pintype "passive"))
    )
    (net (code "62") (name "/VIN") (class "Default")
      (node (ref "C23") (pin "2") (pinfunction "2_2") (pintype "passive"))
      (node (ref "C3") (pin "2") (pinfunction "2_2") (pintype "passive"))
      (node (ref "C36") (pin "2") (pinfunction "2_2") (pintype "passive"))
      (node (ref "C42") (pin "2") (pinfunction "2_2") (pintype "passive"))
      (node (ref "C46") (pin "2") (pinfunction "2_2") (pintype "passive"))
      (node (ref "C6") (pin "2") (pinfunction "2_2") (pintype "passive"))
      (node (ref "D3") (pin "2") (pinfunction "-_2") (pintype "passive"))
      (node (ref "D5") (pin "C") (pinfunction "C_C") (pintype "passive"))
      (node (ref "L1") (pin "1") (pinfunction "P$1_1") (pintype "bidirectional"))
      (node (ref "Q3") (pin "2") (pinfunction "S_2") (pintype "bidirectional"))
      (node (ref "Q30") (pin "2") (pinfunction "S_2") (pintype "bidirectional"))
      (node (ref "R172") (pin "1") (pinfunction "1_1") (pintype "passive"))
      (node (ref "R50") (pin "1") (pinfunction "1_1") (pintype "passive"))
      (node (ref "R51") (pin "1") (pinfunction "1_1") (pintype "passive"))
      (node (ref "R52") (pin "1") (pinfunction "1_1") (pintype "passive"))
      (node (ref "U1") (pin "1") (pinfunction "EN_1") (pintype "bidirectional"))
      (node (ref "U1") (pin "4") (pinfunction "VIN_4") (pintype "bidirectional"))
      (node (ref "U3") (pin "4") (pinfunction "VIN_4") (pintype "bidirectional"))
      (node (ref "U5") (pin "5") (pinfunction "VIN_5") (pintype "bidirectional"))
    )
    (net (code "63") (name "/VIN2") (class "Default")
      (node (ref "C18") (pin "2") (pinfunction "2_2") (pintype "passive"))
      (node (ref "C43") (pin "2") (pinfunction "2_2") (pintype "passive"))
      (node (ref "L5") (pin "1") (pinfunction "1_1") (pintype "bidirectional"))
      (node (ref "Q30") (pin "3") (pinfunction "D_3") (pintype "bidirectional"))
      (node (ref "R49") (pin "2") (pinfunction "2_2") (pintype "passive"))
      (node (ref "R53") (pin "2") (pinfunction "2_2") (pintype "passive"))
      (node (ref "U4") (pin "6") (pinfunction "6-VIN_6") (pintype "bidirectional"))
    )
    (net (code "64") (name "3V3") (class "Default")
      (node (ref "C12") (pin "2") (pinfunction "2_2") (pintype "passive"))
      (node (ref "C13") (pin "1") (pinfunction "1_1") (pintype "passive"))
      (node (ref "C2") (pin "1") (pinfunction "1_1") (pintype "passive"))
      (node (ref "C20") (pin "1") (pinfunction "1_1") (pintype "passive"))
      (node (ref "C26") (pin "1") (pinfunction "1_1") (pintype "passive"))
      (node (ref "C29") (pin "2") (pinfunction "2_2") (pintype "passive"))
      (node (ref "C30") (pin "2") (pinfunction "2_2") (pintype "passive"))
      (node (ref "C31") (pin "2") (pinfunction "2_2") (pintype "passive"))
      (node (ref "C32") (pin "2") (pinfunction "2_2") (pintype "passive"))
      (node (ref "C33") (pin "1") (pinfunction "1_1") (pintype "passive"))
      (node (ref "C4") (pin "2") (pinfunction "2_2") (pintype "passive"))
      (node (ref "C52") (pin "1") (pinfunction "1_1") (pintype "passive"))
      (node (ref "C54") (pin "2") (pinfunction "2_2") (pintype "passive"))
      (node (ref "C7") (pin "2") (pinfunction "2_2") (pintype "passive"))
      (node (ref "C8") (pin "2") (pinfunction "2_2") (pintype "passive"))
      (node (ref "C9") (pin "2") (pinfunction "2_2") (pintype "passive"))
      (node (ref "IC1") (pin "16") (pinfunction "VCC_16") (pintype "bidirectional"))
      (node (ref "J10") (pin "3") (pinfunction "3_3") (pintype "bidirectional"))
      (node (ref "J4") (pin "2") (pinfunction "P$2_2") (pintype "bidirectional"))
      (node (ref "J4") (pin "6") (pinfunction "P$6_6") (pintype "bidirectional"))
      (node (ref "J6") (pin "3") (pinfunction "3_3") (pintype "bidirectional"))
      (node (ref "J7") (pin "3") (pinfunction "3_3") (pintype "bidirectional"))
      (node (ref "L4") (pin "2") (pinfunction "P$2_2") (pintype "bidirectional"))
      (node (ref "P2") (pin "5") (pinfunction "2_5") (pintype "bidirectional"))
      (node (ref "P4") (pin "5") (pinfunction "2_5") (pintype "bidirectional"))
      (node (ref "Q4") (pin "2") (pinfunction "S_2") (pintype "bidirectional"))
      (node (ref "R10") (pin "1") (pinfunction "1_1") (pintype "passive"))
      (node (ref "R16") (pin "1") (pinfunction "1_1") (pintype "passive"))
      (node (ref "R17") (pin "1") (pinfunction "1_1") (pintype "passive"))
      (node (ref "R18") (pin "1") (pinfunction "1_1") (pintype "passive"))
      (node (ref "R20") (pin "1") (pinfunction "1_1") (pintype "passive"))
      (node (ref "R22") (pin "2") (pinfunction "2_2") (pintype "passive"))
      (node (ref "R23") (pin "1") (pinfunction "1_1") (pintype "passive"))
      (node (ref "R24") (pin "1") (pinfunction "1_1") (pintype "passive"))
      (node (ref "R3") (pin "2") (pinfunction "2_2") (pintype "passive"))
      (node (ref "R41") (pin "2") (pinfunction "2_2") (pintype "passive"))
      (node (ref "R42") (pin "2") (pinfunction "2_2") (pintype "passive"))
      (node (ref "R47") (pin "2") (pinfunction "2_2") (pintype "passive"))
      (node (ref "R48") (pin "1") (pinfunction "1_1") (pintype "passive"))
      (node (ref "R5") (pin "1") (pinfunction "1_1") (pintype "passive"))
      (node (ref "R56") (pin "1") (pinfunction "1_1") (pintype "passive"))
      (node (ref "R61") (pin "2") (pinfunction "2_2") (pintype "passive"))
      (node (ref "R67") (pin "1") (pinfunction "1_1") (pintype "passive"))
      (node (ref "SD1") (pin "4") (pinfunction "VDD_4") (pintype "bidirectional"))
      (node (ref "U2") (pin "2") (pinfunction "3V3_2") (pintype "bidirectional"))
      (node (ref "U6") (pin "16") (pinfunction "VCC_16") (pintype "bidirectional"))
      (node (ref "U6") (pin "4") (pinfunction "V3_4") (pintype "bidirectional"))
    )
    (net (code "65") (name "GND") (class "Default")
      (node (ref "C1") (pin "1") (pinfunction "1_1") (pintype "passive"))
      (node (ref "C10") (pin "1") (pinfunction "1_1") (pintype "passive"))
      (node (ref "C11") (pin "2") (pinfunction "2_2") (pintype "passive"))
      (node (ref "C12") (pin "1") (pinfunction "1_1") (pintype "passive"))
      (node (ref "C13") (pin "2") (pinfunction "2_2") (pintype "passive"))
      (node (ref "C14") (pin "2") (pinfunction "2_2") (pintype "passive"))
      (node (ref "C15") (pin "1") (pinfunction "1_1") (pintype "passive"))
      (node (ref "C16") (pin "2") (pinfunction "2_2") (pintype "passive"))
      (node (ref "C17") (pin "1") (pinfunction "1_1") (pintype "passive"))
      (node (ref "C18") (pin "1") (pinfunction "1_1") (pintype "passive"))
      (node (ref "C19") (pin "1") (pinfunction "1_1") (pintype "passive"))
      (node (ref "C2") (pin "2") (pinfunction "2_2") (pintype "passive"))
      (node (ref "C20") (pin "2") (pinfunction "2_2") (pintype "passive"))
      (node (ref "C21") (pin "1") (pinfunction "1_1") (pintype "passive"))
      (node (ref "C22") (pin "1") (pinfunction "1_1") (pintype "passive"))
      (node (ref "C23") (pin "1") (pinfunction "1_1") (pintype "passive"))
      (node (ref "C24") (pin "2") (pinfunction "2_2") (pintype "passive"))
      (node (ref "C25") (pin "2") (pinfunction "2_2") (pintype "passive"))
      (node (ref "C26") (pin "2") (pinfunction "2_2") (pintype "passive"))
      (node (ref "C29") (pin "1") (pinfunction "1_1") (pintype "passive"))
      (node (ref "C3") (pin "1") (pinfunction "1_1") (pintype "passive"))
      (node (ref "C30") (pin "1") (pinfunction "1_1") (pintype "passive"))
      (node (ref "C31") (pin "1") (pinfunction "1_1") (pintype "passive"))
      (node (ref "C32") (pin "1") (pinfunction "1_1") (pintype "passive"))
      (node (ref "C33") (pin "2") (pinfunction "2_2") (pintype "passive"))
      (node (ref "C34") (pin "1") (pinfunction "1_1") (pintype "passive"))
      (node (ref "C35") (pin "1") (pinfunction "1_1") (pintype "passive"))
      (node (ref "C36") (pin "1") (pinfunction "1_1") (pintype "passive"))
      (node (ref "C37") (pin "1") (pinfunction "1_1") (pintype "passive"))
      (node (ref "C4") (pin "1") (pinfunction "1_1") (pintype "passive"))
      (node (ref "C40") (pin "1") (pinfunction "1_1") (pintype "passive"))
      (node (ref "C41") (pin "1") (pinfunction "1_1") (pintype "passive"))
      (node (ref "C42") (pin "1") (pinfunction "1_1") (pintype "passive"))
      (node (ref "C43") (pin "1") (pinfunction "1_1") (pintype "passive"))
      (node (ref "C44") (pin "1") (pinfunction "1_1") (pintype "passive"))
      (node (ref "C45") (pin "1") (pinfunction "1_1") (pintype "passive"))
      (node (ref "C46") (pin "1") (pinfunction "1_1") (pintype "passive"))
      (node (ref "C47") (pin "1") (pinfunction "1_1") (pintype "bidirectional"))
      (node (ref "C48") (pin "1") (pinfunction "1_1") (pintype "bidirectional"))
      (node (ref "C49") (pin "1") (pinfunction "1_1") (pintype "bidirectional"))
      (node (ref "C5") (pin "2") (pinfunction "2_2") (pintype "passive"))
      (node (ref "C50") (pin "2") (pinfunction "2_2") (pintype "passive"))
      (node (ref "C51") (pin "2") (pinfunction "2_2") (pintype "passive"))
      (node (ref "C52") (pin "2") (pinfunction "2_2") (pintype "passive"))
      (node (ref "C54") (pin "1") (pinfunction "1_1") (pintype "passive"))
      (node (ref "C6") (pin "1") (pinfunction "1_1") (pintype "passive"))
      (node (ref "C7") (pin "1") (pinfunction "1_1") (pintype "passive"))
      (node (ref "C76") (pin "1") (pinfunction "1_1") (pintype "passive"))
      (node (ref "C8") (pin "1") (pinfunction "1_1") (pintype "passive"))
      (node (ref "C9") (pin "1") (pinfunction "1_1") (pintype "passive"))
      (node (ref "D2") (pin "+") (pinfunction "+_+") (pintype "passive"))
      (node (ref "D4") (pin "-") (pinfunction "-_-") (pintype "passive"))
      (node (ref "IC1") (pin "3") (pinfunction "A0_3") (pintype "bidirectional"))
      (node (ref "IC1") (pin "4") (pinfunction "A1_4") (pintype "bidirectional"))
      (node (ref "IC1") (pin "5") (pinfunction "A2_5") (pintype "bidirectional"))
      (node (ref "IC1") (pin "8") (pinfunction "VSS_8") (pintype "bidirectional"))
      (node (ref "J1") (pin "P$2") (pinfunction "P$2_P$2") (pintype "bidirectional"))
      (node (ref "J1") (pin "P$3") (pinfunction "P$3_P$3") (pintype "bidirectional"))
      (node (ref "J1") (pin "P$4") (pinfunction "P$4_P$4") (pintype "bidirectional"))
      (node (ref "J10") (pin "4") (pinfunction "4_4") (pintype "bidirectional"))
      (node (ref "J10") (pin "SS1") (pinfunction "SS1_SS1") (pintype "bidirectional"))
      (node (ref "J10") (pin "SS2") (pinfunction "SS2_SS2") (pintype "bidirectional"))
      (node (ref "J2") (pin "P$13") (pinfunction "GND2_P$13") (pintype "bidirectional"))
      (node (ref "J2") (pin "P$15") (pinfunction "GND1_P$15") (pintype "bidirectional"))
      (node (ref "J2") (pin "P$16") (pinfunction "R0_P$16") (pintype "bidirectional"))
      (node (ref "J2") (pin "P$17") (pinfunction "R1_P$17") (pintype "bidirectional"))
      (node (ref "J2") (pin "P$18") (pinfunction "R2_P$18") (pintype "bidirectional"))
      (node (ref "J2") (pin "P$24") (pinfunction "G0_P$24") (pintype "bidirectional"))
      (node (ref "J2") (pin "P$25") (pinfunction "G1_P$25") (pintype "bidirectional"))
      (node (ref "J2") (pin "P$3") (pinfunction "GND3_P$3") (pintype "bidirectional"))
      (node (ref "J2") (pin "P$32") (pinfunction "B0_P$32") (pintype "bidirectional"))
      (node (ref "J2") (pin "P$33") (pinfunction "B1_P$33") (pintype "bidirectional"))
      (node (ref "J2") (pin "P$34") (pinfunction "B2_P$34") (pintype "bidirectional"))
      (node (ref "J2") (pin "P$46") (pinfunction "GND_P$46") (pintype "bidirectional"))
      (node (ref "J3") (pin "A1") (pinfunction "GND_A1") (pintype "bidirectional"))
      (node (ref "J3") (pin "A12") (pinfunction "GND_A12") (pintype "bidirectional"))
      (node (ref "J3") (pin "B1") (pinfunction "GND_B1") (pintype "bidirectional"))
      (node (ref "J3") (pin "B12") (pinfunction "GND_B12") (pintype "bidirectional"))
      (node (ref "J3") (pin "P$6") (pinfunction "P$17_P$6") (pintype "bidirectional"))
      (node (ref "J3") (pin "P$7") (pinfunction "P$18_P$7") (pintype "bidirectional"))
      (node (ref "J3") (pin "P$8") (pinfunction "P$19_P$8") (pintype "bidirectional"))
      (node (ref "J3") (pin "P$9") (pinfunction "P$20_P$9") (pintype "bidirectional"))
      (node (ref "J4") (pin "1") (pinfunction "P$1_1") (pintype "bidirectional"))
      (node (ref "J4") (pin "5") (pinfunction "P$5_5") (pintype "bidirectional"))
      (node (ref "J5") (pin "P$3") (pinfunction "P$3_P$3") (pintype "bidirectional"))
      (node (ref "J5") (pin "P$4") (pinfunction "P$4_P$4") (pintype "bidirectional"))
      (node (ref "J6") (pin "4") (pinfunction "4_4") (pintype "bidirectional"))
      (node (ref "J6") (pin "SS1") (pinfunction "SS1_SS1") (pintype "bidirectional"))
      (node (ref "J6") (pin "SS2") (pinfunction "SS2_SS2") (pintype "bidirectional"))
      (node (ref "J7") (pin "4") (pinfunction "4_4") (pintype "bidirectional"))
      (node (ref "J7") (pin "SS1") (pinfunction "SS1_SS1") (pintype "bidirectional"))
      (node (ref "J7") (pin "SS2") (pinfunction "SS2_SS2") (pintype "bidirectional"))
      (node (ref "K1") (pin "1") (pinfunction "1_1") (pintype "passive"))
      (node (ref "K4") (pin "1") (pinfunction "1_1") (pintype "passive"))
      (node (ref "LED1") (pin "-") (pinfunction "-_-") (pintype "passive"))
      (node (ref "P2") (pin "4") (pinfunction "3_4") (pintype "bidirectional"))
      (node (ref "P2") (pin "7") (pinfunction "7_7") (pintype "bidirectional"))
      (node (ref "P2") (pin "8") (pinfunction "8_8") (pintype "bidirectional"))
      (node (ref "P4") (pin "4") (pinfunction "3_4") (pintype "bidirectional"))
      (node (ref "P4") (pin "7") (pinfunction "7_7") (pintype "bidirectional"))
      (node (ref "P4") (pin "8") (pinfunction "8_8") (pintype "bidirectional"))
      (node (ref "Q2") (pin "2") (pinfunction "P$2_2") (pintype "bidirectional"))
      (node (ref "Q5") (pin "2") (pinfunction "E_2") (pintype "passive"))
      (node (ref "Q6") (pin "2") (pinfunction "E_2") (pintype "passive"))
      (node (ref "R13") (pin "1") (pinfunction "1_1") (pintype "passive"))
      (node (ref "R14") (pin "2") (pinfunction "2_2") (pintype "passive"))
      (node (ref "R15") (pin "2") (pinfunction "2_2") (pintype "passive"))
      (node (ref "R2") (pin "2") (pinfunction "2_2") (pintype "passive"))
      (node (ref "R21") (pin "2") (pinfunction "2_2") (pintype "passive"))
      (node (ref "R27") (pin "2") (pinfunction "2_2") (pintype "passive"))
      (node (ref "R28") (pin "2") (pinfunction "2_2") (pintype "passive"))
      (node (ref "R29") (pin "2") (pinfunction "2_2") (pintype "passive"))
      (node (ref "R31") (pin "1") (pinfunction "1_1") (pintype "passive"))
      (node (ref "R33") (pin "1") (pinfunction "1_1") (pintype "passive"))
      (node (ref "R35") (pin "1") (pinfunction "1_1") (pintype "passive"))
      (node (ref "R37") (pin "1") (pinfunction "1_1") (pintype "passive"))
      (node (ref "R43") (pin "2") (pinfunction "2_2") (pintype "passive"))
      (node (ref "R44") (pin "1") (pinfunction "1_1") (pintype "passive"))
      (node (ref "R55") (pin "1") (pinfunction "1_1") (pintype "passive"))
      (node (ref "R58") (pin "1") (pinfunction "1_1") (pintype "passive"))
      (node (ref "R91") (pin "2") (pinfunction "2_2") (pintype "passive"))
      (node (ref "SD1") (pin "6") (pinfunction "VSS_6") (pintype "bidirectional"))
      (node (ref "SD1") (pin "G1") (pinfunction "G1_G1") (pintype "bidirectional"))
      (node (ref "SD1") (pin "G2") (pinfunction "G2_G2") (pintype "bidirectional"))
      (node (ref "SD1") (pin "G3") (pinfunction "G3_G3") (pintype "bidirectional"))
      (node (ref "SD1") (pin "G4") (pinfunction "G4_G4") (pintype "bidirectional"))
      (node (ref "U1") (pin "2") (pinfunction "GND_2") (pintype "bidirectional"))
      (node (ref "U11") (pin "7") (pinfunction "GND_7") (pintype "bidirectional"))
      (node (ref "U11") (pin "9") (pinfunction "PE_9") (pintype "bidirectional"))
      (node (ref "U2") (pin "1") (pinfunction "GND1_1") (pintype "bidirectional"))
      (node (ref "U2") (pin "40") (pinfunction "GND2_40") (pintype "bidirectional"))
      (node (ref "U2") (pin "41") (pinfunction "GND3_41") (pintype "bidirectional"))
      (node (ref "U2") (pin "42") (pinfunction "GND4_42") (pintype "bidirectional"))
      (node (ref "U2") (pin "43") (pinfunction "GND5_43") (pintype "bidirectional"))
      (node (ref "U2") (pin "44") (pinfunction "GND6_44") (pintype "bidirectional"))
      (node (ref "U2") (pin "45") (pinfunction "GND7_45") (pintype "bidirectional"))
      (node (ref "U2") (pin "46") (pinfunction "GND8_46") (pintype "bidirectional"))
      (node (ref "U2") (pin "47") (pinfunction "GND9_47") (pintype "bidirectional"))
      (node (ref "U2") (pin "48") (pinfunction "GND10_48") (pintype "bidirectional"))
      (node (ref "U2") (pin "49") (pinfunction "GND11_49") (pintype "bidirectional"))
      (node (ref "U26") (pin "2") (pinfunction "GND_2") (pintype "bidirectional"))
      (node (ref "U3") (pin "2") (pinfunction "GND_2") (pintype "bidirectional"))
      (node (ref "U4") (pin "2") (pinfunction "2-GND_2") (pintype "bidirectional"))
      (node (ref "U5") (pin "2") (pinfunction "GND_2") (pintype "bidirectional"))
      (node (ref "U6") (pin "1") (pinfunction "GND_1") (pintype "bidirectional"))
    )
    (net (code "66") (name "IO19_I2C_SDA") (class "Default")
      (node (ref "IC1") (pin "2") (pinfunction "SDA_2") (pintype "bidirectional"))
      (node (ref "J4") (pin "7") (pinfunction "P$7_7") (pintype "bidirectional"))
      (node (ref "J6") (pin "2") (pinfunction "2_2") (pintype "bidirectional"))
      (node (ref "P2") (pin "2") (pinfunction "5_2") (pintype "bidirectional"))
      (node (ref "P4") (pin "2") (pinfunction "5_2") (pintype "bidirectional"))
      (node (ref "R41") (pin "1") (pinfunction "1_1") (pintype "passive"))
      (node (ref "U2") (pin "13") (pinfunction "IO19_13") (pintype "bidirectional"))
    )
    (net (code "67") (name "IO20_I2C_SCL") (class "Default")
      (node (ref "IC1") (pin "1") (pinfunction "SCL_1") (pintype "bidirectional"))
      (node (ref "J4") (pin "8") (pinfunction "P$8_8") (pintype "bidirectional"))
      (node (ref "J6") (pin "1") (pinfunction "1_1") (pintype "bidirectional"))
      (node (ref "P2") (pin "1") (pinfunction "6_1") (pintype "bidirectional"))
      (node (ref "P4") (pin "1") (pinfunction "6_1") (pintype "bidirectional"))
      (node (ref "R42") (pin "1") (pinfunction "1_1") (pintype "passive"))
      (node (ref "U2") (pin "14") (pinfunction "IO20_14") (pintype "bidirectional"))
    )
    (net (code "68") (name "Net-(D1-+)") (class "Default")
      (node (ref "C27") (pin "2") (pinfunction "2_2") (pintype "passive"))
      (node (ref "C28") (pin "2") (pinfunction "2_2") (pintype "passive"))
      (node (ref "D1") (pin "1") (pinfunction "+_1") (pintype "passive"))
      (node (ref "L1") (pin "2") (pinfunction "P$2_2") (pintype "bidirectional"))
      (node (ref "U5") (pin "1") (pinfunction "LX_1") (pintype "bidirectional"))
    )
    (net (code "69") (name "Net-(D6-+)") (class "Default")
      (node (ref "D6") (pin "1") (pinfunction "+_1") (pintype "passive"))
      (node (ref "L5") (pin "2") (pinfunction "2_2") (pintype "bidirectional"))
      (node (ref "U4") (pin "1") (pinfunction "1-SW_1") (pintype "bidirectional"))
    )
    (net (code "70") (name "Net-(IC1-RESET{slash})") (class "Default")
      (node (ref "IC1") (pin "15") (pinfunction "RESET/_15") (pintype "bidirectional"))
      (node (ref "R61") (pin "1") (pinfunction "1_1") (pintype "passive"))
    )
    (net (code "71") (name "Net-(J2-DCLK)") (class "Default")
      (node (ref "C1") (pin "2") (pinfunction "2_2") (pintype "passive"))
      (node (ref "J2") (pin "P$14") (pinfunction "DCLK_P$14") (pintype "bidirectional"))
      (node (ref "R38") (pin "2") (pinfunction "2_2") (pintype "passive"))
    )
    (net (code "72") (name "Net-(J2-DITHB)") (class "Default")
      (node (ref "J2") (pin "P$4") (pinfunction "DITHB_P$4") (pintype "bidirectional"))
      (node (ref "R39") (pin "1") (pinfunction "1_1") (pintype "passive"))
    )
    (net (code "73") (name "Net-(J2-MODE)") (class "Default")
      (node (ref "J2") (pin "P$43") (pinfunction "MODE_P$43") (pintype "bidirectional"))
      (node (ref "R36") (pin "1") (pinfunction "1_1") (pintype "passive"))
      (node (ref "R37") (pin "2") (pinfunction "2_2") (pintype "passive"))
    )
    (net (code "74") (name "Net-(J2-VCOM)") (class "Default")
      (node (ref "J2") (pin "P$45") (pinfunction "VCOM_P$45") (pintype "bidirectional"))
      (node (ref "R25") (pin "2") (pinfunction "2_2") (pintype "passive"))
    )
    (net (code "75") (name "Net-(J2-VCOM1)") (class "Default")
      (node (ref "J2") (pin "P$5") (pinfunction "VCOM1_P$5") (pintype "bidirectional"))
      (node (ref "R26") (pin "2") (pinfunction "2_2") (pintype "passive"))
    )
    (net (code "76") (name "Net-(J3-CC1)") (class "Default")
      (node (ref "J3") (pin "A5") (pinfunction "CC1_A5") (pintype "bidirectional"))
      (node (ref "R13") (pin "2") (pinfunction "2_2") (pintype "passive"))
    )
    (net (code "77") (name "Net-(J3-CC2)") (class "Default")
      (node (ref "J3") (pin "B5") (pinfunction "CC2_B5") (pintype "bidirectional"))
      (node (ref "R14") (pin "1") (pinfunction "1_1") (pintype "passive"))
    )
    (net (code "78") (name "Net-(L2-P$1)") (class "Default")
      (node (ref "L2") (pin "1") (pinfunction "P$1_1") (pintype "bidirectional"))
      (node (ref "U3") (pin "3") (pinfunction "SW_3") (pintype "bidirectional"))
    )
    (net (code "79") (name "Net-(L4-P$1)") (class "Default")
      (node (ref "L4") (pin "1") (pinfunction "P$1_1") (pintype "bidirectional"))
      (node (ref "U1") (pin "3") (pinfunction "SW_3") (pintype "bidirectional"))
    )
    (net (code "80") (name "Net-(LED1-Pad+)") (class "Default")
      (node (ref "LED1") (pin "+") (pinfunction "+_+") (pintype "passive"))
      (node (ref "R3") (pin "1") (pinfunction "1_1") (pintype "passive"))
    )
    (net (code "81") (name "Net-(Q1-P$2)") (class "Default")
      (node (ref "C35") (pin "2") (pinfunction "2_2") (pintype "passive"))
      (node (ref "Q1") (pin "2") (pinfunction "P$2_2") (pintype "bidirectional"))
      (node (ref "R7") (pin "1") (pinfunction "1_1") (pintype "passive"))
    )
    (net (code "82") (name "Net-(Q1-P$3)") (class "Default")
      (node (ref "C27") (pin "1") (pinfunction "1_1") (pintype "passive"))
      (node (ref "Q1") (pin "3") (pinfunction "P$3_3") (pintype "bidirectional"))
    )
    (net (code "83") (name "Net-(Q2-P$1)") (class "Default")
      (node (ref "C34") (pin "2") (pinfunction "2_2") (pintype "passive"))
      (node (ref "Q2") (pin "1") (pinfunction "P$1_1") (pintype "bidirectional"))
      (node (ref "R6") (pin "1") (pinfunction "1_1") (pintype "passive"))
    )
    (net (code "84") (name "Net-(Q2-P$3)") (class "Default")
      (node (ref "C28") (pin "1") (pinfunction "1_1") (pintype "passive"))
      (node (ref "Q2") (pin "3") (pinfunction "P$3_3") (pintype "bidirectional"))
    )
    (net (code "85") (name "Net-(Q3-G)") (class "Default")
      (node (ref "Q3") (pin "1") (pinfunction "G_1") (pintype "bidirectional"))
      (node (ref "R44") (pin "2") (pinfunction "2_2") (pintype "passive"))
      (node (ref "R45") (pin "1") (pinfunction "1_1") (pintype "passive"))
    )
    (net (code "86") (name "Net-(Q4-G)") (class "Default")
      (node (ref "Q4") (pin "1") (pinfunction "G_1") (pintype "bidirectional"))
      (node (ref "Q6") (pin "3") (pinfunction "C_3") (pintype "passive"))
      (node (ref "R48") (pin "2") (pinfunction "2_2") (pintype "passive"))
    )
    (net (code "87") (name "Net-(Q5-B)") (class "Default")
      (node (ref "Q5") (pin "1") (pinfunction "B_1") (pintype "passive"))
      (node (ref "R11") (pin "1") (pinfunction "1_1") (pintype "passive"))
      (node (ref "R58") (pin "2") (pinfunction "2_2") (pintype "passive"))
    )
    (net (code "88") (name "Net-(Q6-B)") (class "Default")
      (node (ref "Q6") (pin "1") (pinfunction "B_1") (pintype "passive"))
      (node (ref "R54") (pin "1") (pinfunction "1_1") (pintype "passive"))
      (node (ref "R55") (pin "2") (pinfunction "2_2") (pintype "passive"))
      (node (ref "R60") (pin "1") (pinfunction "1_1") (pintype "passive"))
    )
    (net (code "89") (name "Net-(Q9-B)") (class "Default")
      (node (ref "Q9") (pin "1") (pinfunction "B_1") (pintype "passive"))
      (node (ref "R75") (pin "1") (pinfunction "1_1") (pintype "passive"))
    )
    (net (code "90") (name "Net-(Q10-B)") (class "Default")
      (node (ref "Q10") (pin "1") (pinfunction "B_1") (pintype "passive"))
      (node (ref "R74") (pin "1") (pinfunction "1_1") (pintype "passive"))
    )
    (net (code "91") (name "Net-(Q30-G)") (class "Default")
      (node (ref "Q30") (pin "1") (pinfunction "G_1") (pintype "bidirectional"))
      (node (ref "Q5") (pin "3") (pinfunction "C_3") (pintype "passive"))
      (node (ref "R172") (pin "2") (pinfunction "2_2") (pintype "passive"))
    )
    (net (code "92") (name "Net-(SD1-DATA1)") (class "Default")
      (node (ref "R17") (pin "2") (pinfunction "2_2") (pintype "passive"))
      (node (ref "SD1") (pin "8") (pinfunction "DATA1_8") (pintype "bidirectional"))
    )
    (net (code "93") (name "Net-(SD1-DATA2)") (class "Default")
      (node (ref "R16") (pin "2") (pinfunction "2_2") (pintype "passive"))
      (node (ref "SD1") (pin "1") (pinfunction "DATA2_1") (pintype "bidirectional"))
    )
    (net (code "94") (name "Net-(U1-FB)") (class "Default")
      (node (ref "R20") (pin "2") (pinfunction "2_2") (pintype "passive"))
      (node (ref "R21") (pin "1") (pinfunction "1_1") (pintype "passive"))
      (node (ref "U1") (pin "5") (pinfunction "FB_5") (pintype "bidirectional"))
    )
    (net (code "95") (name "Net-(U3-EN)") (class "Default")
      (node (ref "R49") (pin "1") (pinfunction "1_1") (pintype "passive"))
      (node (ref "R51") (pin "2") (pinfunction "2_2") (pintype "passive"))
      (node (ref "U3") (pin "1") (pinfunction "EN_1") (pintype "bidirectional"))
    )
    (net (code "96") (name "Net-(U3-FB)") (class "Default")
      (node (ref "R30") (pin "2") (pinfunction "2_2") (pintype "passive"))
      (node (ref "R43") (pin "1") (pinfunction "1_1") (pintype "passive"))
      (node (ref "U3") (pin "5") (pinfunction "FB_5") (pintype "bidirectional"))
    )
    (net (code "97") (name "Net-(U5-EN)") (class "Default")
      (node (ref "R52") (pin "2") (pinfunction "2_2") (pintype "passive"))
      (node (ref "R53") (pin "1") (pinfunction "1_1") (pintype "passive"))
      (node (ref "U5") (pin "4") (pinfunction "EN_4") (pintype "bidirectional"))
    )
    (net (code "98") (name "Net-(U5-FB)") (class "Default")
      (node (ref "R1") (pin "2") (pinfunction "2_2") (pintype "passive"))
      (node (ref "R2") (pin "1") (pinfunction "1_1") (pintype "passive"))
      (node (ref "U5") (pin "3") (pinfunction "FB_3") (pintype "bidirectional"))
    )
    (net (code "99") (name "Net-(U6-RXD)") (class "Default")
      (node (ref "R71") (pin "2") (pinfunction "2_2") (pintype "passive"))
      (node (ref "U6") (pin "3") (pinfunction "RXD_3") (pintype "bidirectional"))
    )
    (net (code "100") (name "Net-(U6-TXD)") (class "Default")
      (node (ref "R72") (pin "2") (pinfunction "2_2") (pintype "passive"))
      (node (ref "U6") (pin "2") (pinfunction "TXD_2") (pintype "bidirectional"))
    )
    (net (code "101") (name "Net-(U11-VON)") (class "Default")
      (node (ref "C39") (pin "2") (pinfunction "2_2") (pintype "passive"))
      (node (ref "U11") (pin "5") (pinfunction "VON_5") (pintype "bidirectional"))
    )
    (net (code "102") (name "Net-(U11-VOP)") (class "Default")
      (node (ref "C38") (pin "2") (pinfunction "2_2") (pintype "passive"))
      (node (ref "U11") (pin "8") (pinfunction "VOP_8") (pintype "bidirectional"))
    )
    (net (code "103") (name "Net-(U26-PROG)") (class "Default")
      (node (ref "R15") (pin "1") (pinfunction "1_1") (pintype "passive"))
      (node (ref "U26") (pin "5") (pinfunction "PROG_5") (pintype "bidirectional"))
    )
    (net (code "104") (name "unconnected-(IC1-IO4-Pad11)") (class "Default")
      (node (ref "IC1") (pin "11") (pinfunction "IO4_11") (pintype "bidirectional"))
    )
    (net (code "105") (name "unconnected-(IC1-IO5-Pad12)") (class "Default")
      (node (ref "IC1") (pin "12") (pinfunction "IO5_12") (pintype "bidirectional"))
    )
    (net (code "106") (name "unconnected-(IC1-IO6-Pad13)") (class "Default")
      (node (ref "IC1") (pin "13") (pinfunction "IO6_13") (pintype "bidirectional"))
    )
    (net (code "107") (name "unconnected-(IC1-IO7-Pad14)") (class "Default")
      (node (ref "IC1") (pin "14") (pinfunction "IO7_14") (pintype "bidirectional"))
    )
    (net (code "108") (name "unconnected-(J2-GND4-PadP$51)") (class "Default")
      (node (ref "J2") (pin "P$51") (pinfunction "GND4_P$51") (pintype "bidirectional"))
    )
    (net (code "109") (name "unconnected-(J2-GND5-PadP$52)") (class "Default")
      (node (ref "J2") (pin "P$52") (pinfunction "GND5_P$52") (pintype "bidirectional"))
    )
    (net (code "110") (name "unconnected-(J2-NC-PadP$6)") (class "Default")
      (node (ref "J2") (pin "P$6") (pinfunction "NC_P$6") (pintype "bidirectional"))
    )
    (net (code "111") (name "unconnected-(J2-NC1-PadP$2)") (class "Default")
      (node (ref "J2") (pin "P$2") (pinfunction "NC1_P$2") (pintype "bidirectional"))
    )
    (net (code "112") (name "unconnected-(J2-NC2-PadP$1)") (class "Default")
      (node (ref "J2") (pin "P$1") (pinfunction "NC2_P$1") (pintype "bidirectional"))
    )
    (net (code "113") (name "unconnected-(J3-SBU1-PadA8)") (class "Default")
      (node (ref "J3") (pin "A8") (pinfunction "SBU1_A8") (pintype "bidirectional"))
    )
    (net (code "114") (name "unconnected-(J3-SBU2-PadB8)") (class "Default")
      (node (ref "J3") (pin "B8") (pinfunction "SBU2_B8") (pintype "bidirectional"))
    )
    (net (code "115") (name "unconnected-(J4-P$3-Pad3)") (class "Default")
      (node (ref "J4") (pin "3") (pinfunction "P$3_3") (pintype "bidirectional"))
    )
    (net (code "116") (name "unconnected-(J7-Pad2)") (class "Default")
      (node (ref "J7") (pin "2") (pinfunction "2_2") (pintype "bidirectional"))
    )
    (net (code "117") (name "unconnected-(SD1-CDN-Pad9)") (class "Default")
      (node (ref "SD1") (pin "9") (pinfunction "CDN_9") (pintype "bidirectional"))
    )
    (net (code "118") (name "unconnected-(U2-NC1-Pad28)") (class "Default")
      (node (ref "U2") (pin "28") (pinfunction "NC1_28") (pintype "bidirectional"))
    )
    (net (code "119") (name "unconnected-(U2-NC2-Pad29)") (class "Default")
      (node (ref "U2") (pin "29") (pinfunction "NC2_29") (pintype "bidirectional"))
    )
    (net (code "120") (name "unconnected-(U2-NC3-Pad30)") (class "Default")
      (node (ref "U2") (pin "30") (pinfunction "NC3_30") (pintype "bidirectional"))
    )
    (net (code "121") (name "unconnected-(U6-CTS#-Pad9)") (class "Default")
      (node (ref "U6") (pin "9") (pinfunction "CTS#_9") (pintype "bidirectional"))
    )
    (net (code "122") (name "unconnected-(U6-DCD#-Pad12)") (class "Default")
      (node (ref "U6") (pin "12") (pinfunction "DCD#_12") (pintype "bidirectional"))
    )
    (net (code "123") (name "unconnected-(U6-DSR#-Pad10)") (class "Default")
      (node (ref "U6") (pin "10") (pinfunction "DSR#_10") (pintype "bidirectional"))
    )
    (net (code "124") (name "unconnected-(U6-RI#-Pad11)") (class "Default")
      (node (ref "U6") (pin "11") (pinfunction "RI#_11") (pintype "bidirectional"))
    )
    (net (code "125") (name "unconnected-(U6-RS232-Pad15)") (class "Default")
      (node (ref "U6") (pin "15") (pinfunction "RS232_15") (pintype "bidirectional"))
    )
    (net (code "126") (name "unconnected-(U6-XI-Pad7)") (class "Default")
      (node (ref "U6") (pin "7") (pinfunction "XI_7") (pintype "bidirectional"))
    )
    (net (code "127") (name "unconnected-(U6-XO-Pad8)") (class "Default")
      (node (ref "U6") (pin "8") (pinfunction "XO_8") (pintype "bidirectional"))
    )
    (net (code "128") (name "unconnected-(U26-GHRG-Pad1)") (class "Default")
      (node (ref "U26") (pin "1") (pinfunction "GHRG_1") (pintype "bidirectional"))
    )
  )
)
